# REV4.net
KiCad netlist of a schematic drawn in EAGLE
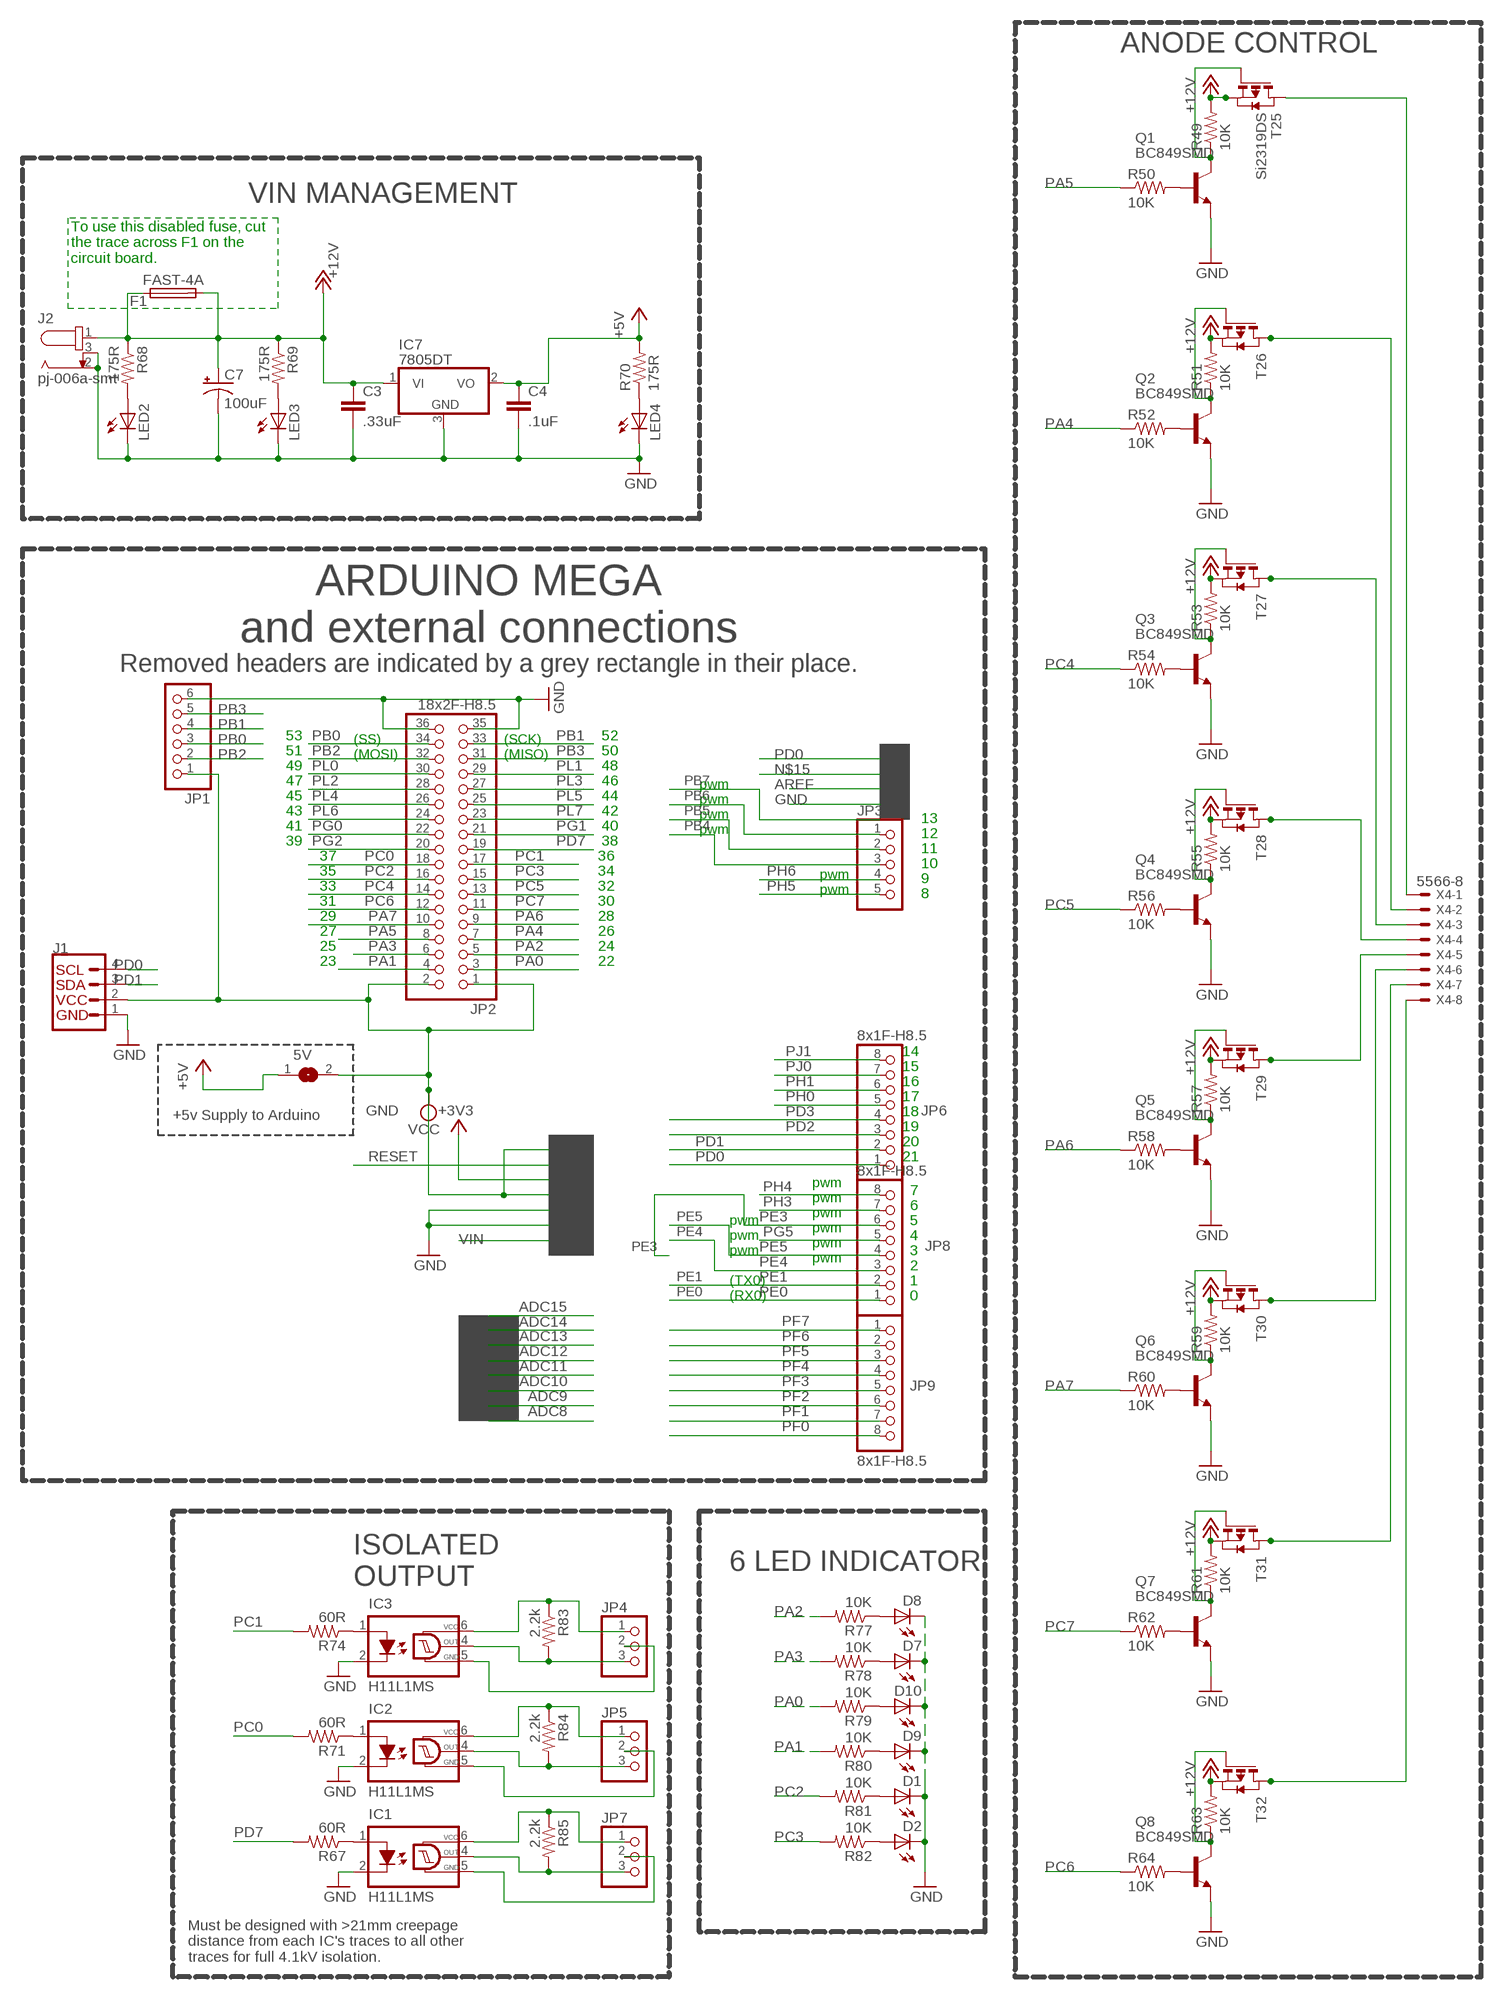
[diagram p0: schematic, sheet 1, part 1 of 2]
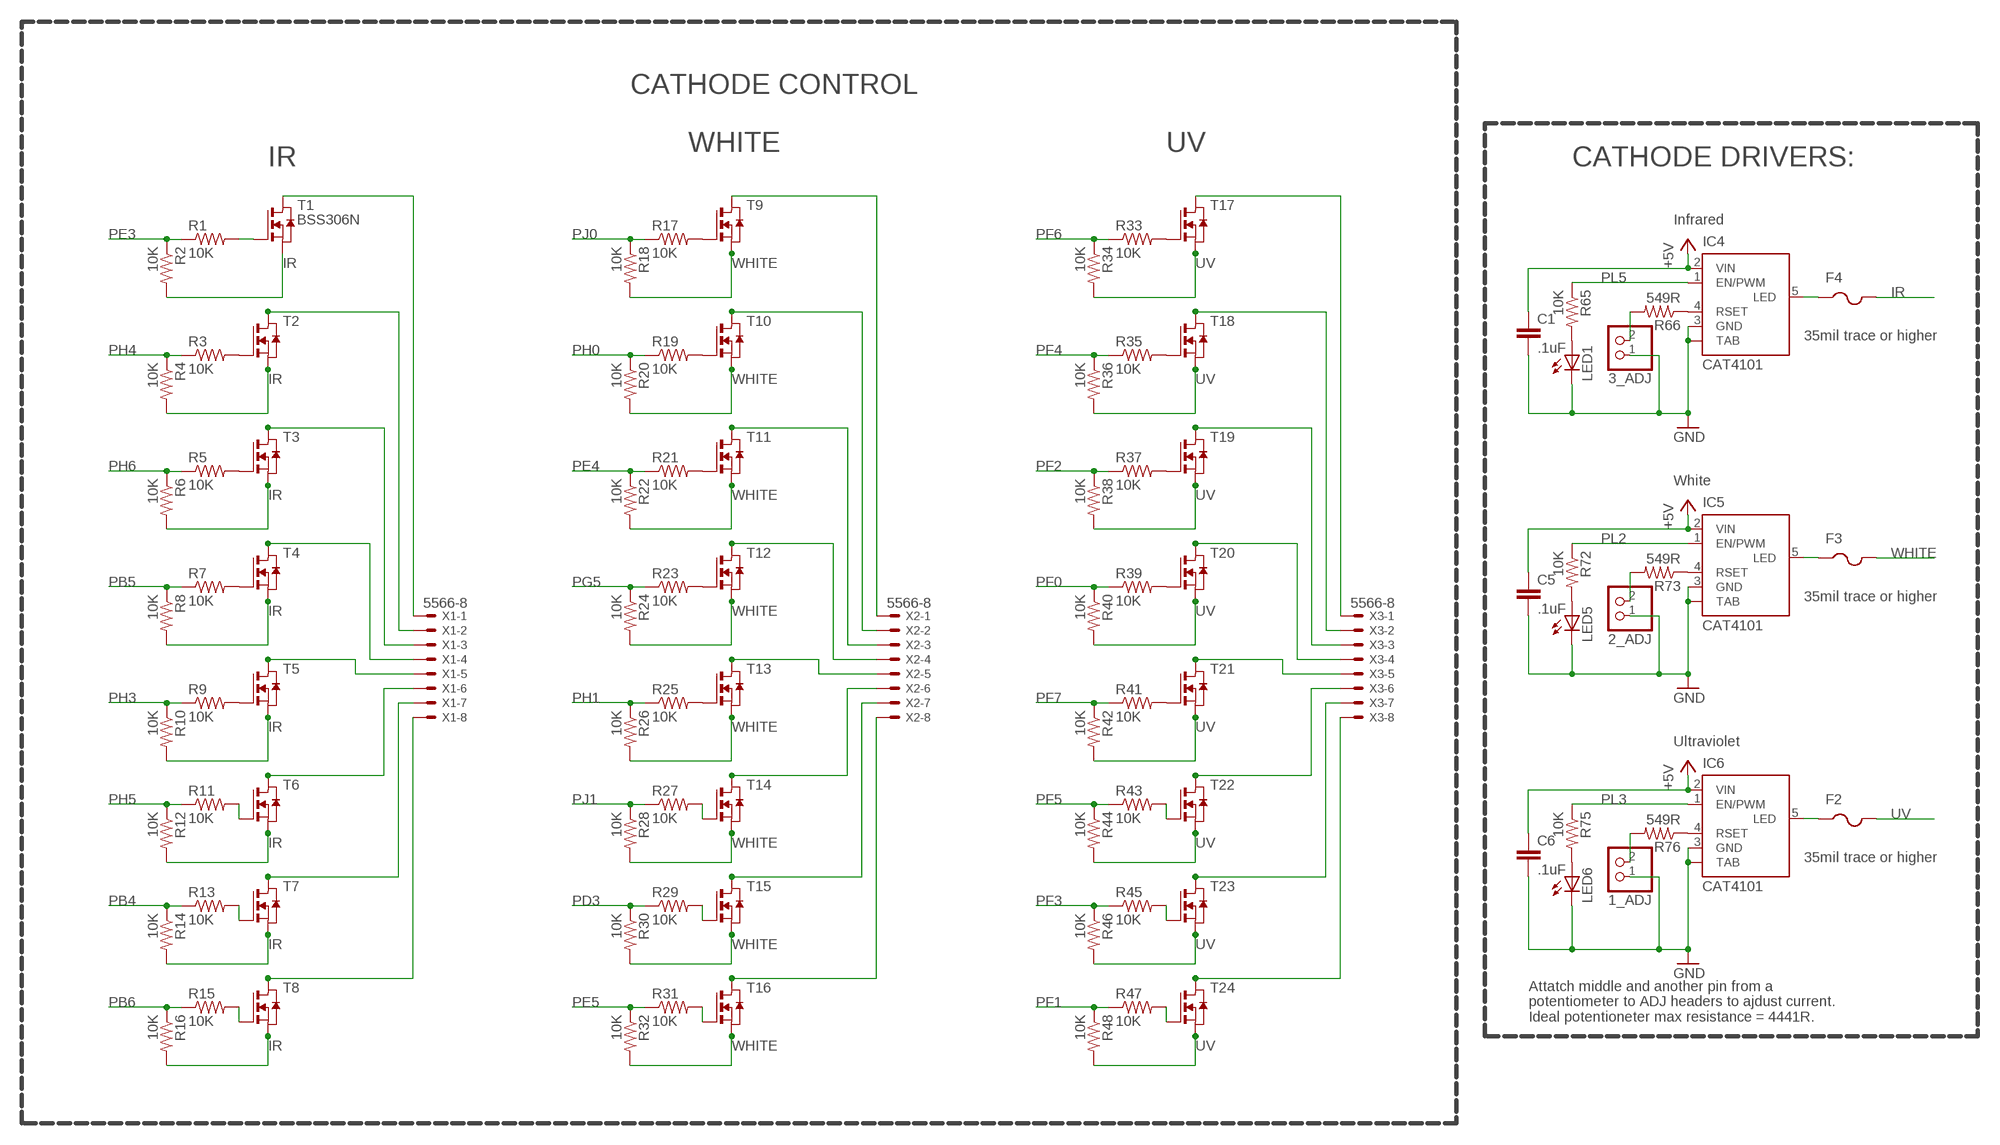
[diagram p1: schematic, sheet 1, part 2 of 2]

(export (version "E")
  (design (tool "Eeschema 10.0.6"))
  (components
    (comp (ref "1_ADJ")
      (value "PINHD-1X2")
      (footprint "eagle-import:1X02")
      (libsource (lib "eagle-import") (part "PINHD-1X2"))
    )
    (comp (ref "2_ADJ")
      (value "PINHD-1X2")
      (footprint "eagle-import:1X02")
      (libsource (lib "eagle-import") (part "PINHD-1X2"))
    )
    (comp (ref "3_ADJ")
      (value "PINHD-1X2")
      (footprint "eagle-import:1X02")
      (libsource (lib "eagle-import") (part "PINHD-1X2"))
    )
    (comp (ref "5V") (value "SJ") (footprint "eagle-import:SJ") (libsource (lib "eagle-import") (part "SJ")))
    (comp (ref "C1")
      (value ".1uF")
      (footprint "eagle-import:C0805")
      (libsource (lib "eagle-import") (part "C"))
    )
    (comp (ref "C3")
      (value ".33uF")
      (footprint "eagle-import:C0805")
      (libsource (lib "eagle-import") (part "C"))
    )
    (comp (ref "C4")
      (value ".1uF")
      (footprint "eagle-import:C0805")
      (libsource (lib "eagle-import") (part "C"))
    )
    (comp (ref "C5")
      (value ".1uF")
      (footprint "eagle-import:C0805")
      (libsource (lib "eagle-import") (part "C"))
    )
    (comp (ref "C6")
      (value ".1uF")
      (footprint "eagle-import:C0805")
      (libsource (lib "eagle-import") (part "C"))
    )
    (comp (ref "C7")
      (value "100uF")
      (footprint "eagle-import:153CLV-0807")
      (libsource (lib "eagle-import") (part "CPOL-US153CLV-0807"))
    )
    (comp (ref "D1")
      (value "LEDSMT1206")
      (footprint "eagle-import:1206")
      (libsource (lib "eagle-import") (part "LEDSMT1206"))
    )
    (comp (ref "D2")
      (value "LEDSMT1206")
      (footprint "eagle-import:1206")
      (libsource (lib "eagle-import") (part "LEDSMT1206"))
    )
    (comp (ref "D7")
      (value "LEDSMT1206")
      (footprint "eagle-import:1206")
      (libsource (lib "eagle-import") (part "LEDSMT1206"))
    )
    (comp (ref "D8")
      (value "LEDSMT1206")
      (footprint "eagle-import:1206")
      (libsource (lib "eagle-import") (part "LEDSMT1206"))
    )
    (comp (ref "D9")
      (value "LEDSMT1206")
      (footprint "eagle-import:1206")
      (libsource (lib "eagle-import") (part "LEDSMT1206"))
    )
    (comp (ref "D10")
      (value "LEDSMT1206")
      (footprint "eagle-import:1206")
      (libsource (lib "eagle-import") (part "LEDSMT1206"))
    )
    (comp (ref "F1")
      (value "FAST-4A")
      (footprint "eagle-import:FUSE_MF-SMDF050")
      (libsource (lib "eagle-import") (part "FUSE_MF-SMDF050"))
    )
    (comp (ref "F2")
      (value "PTCFUSE-1812")
      (footprint "eagle-import:1812")
      (libsource (lib "eagle-import") (part "PTCFUSE-1812"))
    )
    (comp (ref "F3")
      (value "PTCFUSE-1812")
      (footprint "eagle-import:1812")
      (libsource (lib "eagle-import") (part "PTCFUSE-1812"))
    )
    (comp (ref "F4")
      (value "PTCFUSE-1812")
      (footprint "eagle-import:1812")
      (libsource (lib "eagle-import") (part "PTCFUSE-1812"))
    )
    (comp (ref "IC1")
      (value "H11L1MS")
      (footprint "eagle-import:DIL6-SMD")
      (libsource (lib "eagle-import") (part "H11LMS1"))
    )
    (comp (ref "IC2")
      (value "H11L1MS")
      (footprint "eagle-import:DIL6-SMD")
      (libsource (lib "eagle-import") (part "H11LMS1"))
    )
    (comp (ref "IC3")
      (value "H11L1MS")
      (footprint "eagle-import:DIL6-SMD")
      (libsource (lib "eagle-import") (part "H11LMS1"))
    )
    (comp (ref "IC4")
      (value "CAT4101")
      (footprint "eagle-import:TO263_5")
      (fields (field (name "MPN") "CAT4101TV-T75"))
      (libsource (lib "eagle-import") (part "CAT4101"))
    )
    (comp (ref "IC5")
      (value "CAT4101")
      (footprint "eagle-import:TO263_5")
      (fields (field (name "MPN") "CAT4101TV-T75"))
      (libsource (lib "eagle-import") (part "CAT4101"))
    )
    (comp (ref "IC6")
      (value "CAT4101")
      (footprint "eagle-import:TO263_5")
      (fields (field (name "MPN") "CAT4101TV-T75"))
      (libsource (lib "eagle-import") (part "CAT4101"))
    )
    (comp (ref "IC7")
      (value "7805DT")
      (footprint "eagle-import:TO252")
      (libsource (lib "eagle-import") (part "78DT05"))
    )
    (comp (ref "J1")
      (value "I2C_STANDARD")
      (footprint "eagle-import:1X04")
      (libsource (lib "eagle-import") (part "I2C_STANDARD"))
    )
    (comp (ref "J2")
      (value "pj-006a-smt")
      (footprint "eagle-import:69410X210102")
      (libsource (lib "eagle-import") (part "694106210102"))
    )
    (comp (ref "JP1")
      (value "PINHD-1X6")
      (footprint "eagle-import:1X06")
      (libsource (lib "eagle-import") (part "PINHD-1X6"))
    )
    (comp (ref "JP2")
      (value "18x2F-H8.5")
      (footprint "eagle-import:2X18")
      (libsource (lib "eagle-import") (part "PINHD-2X18"))
    )
    (comp (ref "JP3")
      (value "PINHD-1X5")
      (footprint "eagle-import:1X05")
      (libsource (lib "eagle-import") (part "PINHD-1X5"))
    )
    (comp (ref "JP4")
      (value "PINHD-1X3")
      (footprint "eagle-import:1X03")
      (libsource (lib "eagle-import") (part "PINHD-1X3"))
    )
    (comp (ref "JP5")
      (value "PINHD-1X3")
      (footprint "eagle-import:1X03")
      (libsource (lib "eagle-import") (part "PINHD-1X3"))
    )
    (comp (ref "JP6")
      (value "8x1F-H8.5")
      (footprint "eagle-import:1X08")
      (libsource (lib "eagle-import") (part "PINHD-1X8"))
    )
    (comp (ref "JP7")
      (value "PINHD-1X3")
      (footprint "eagle-import:1X03")
      (libsource (lib "eagle-import") (part "PINHD-1X3"))
    )
    (comp (ref "JP8")
      (value "8x1F-H8.5")
      (footprint "eagle-import:1X08")
      (libsource (lib "eagle-import") (part "PINHD-1X8"))
    )
    (comp (ref "JP9")
      (value "8x1F-H8.5")
      (footprint "eagle-import:1X08")
      (libsource (lib "eagle-import") (part "PINHD-1X8"))
    )
    (comp (ref "LED1")
      (value "LEDSMT1206")
      (footprint "eagle-import:1206")
      (libsource (lib "eagle-import") (part "LEDSMT1206"))
    )
    (comp (ref "LED2")
      (value "LEDSMT1206")
      (footprint "eagle-import:1206")
      (libsource (lib "eagle-import") (part "LEDSMT1206"))
    )
    (comp (ref "LED3")
      (value "LEDSMT1206")
      (footprint "eagle-import:1206")
      (libsource (lib "eagle-import") (part "LEDSMT1206"))
    )
    (comp (ref "LED4")
      (value "LEDSMT1206")
      (footprint "eagle-import:1206")
      (libsource (lib "eagle-import") (part "LEDSMT1206"))
    )
    (comp (ref "LED5")
      (value "LEDSMT1206")
      (footprint "eagle-import:1206")
      (libsource (lib "eagle-import") (part "LEDSMT1206"))
    )
    (comp (ref "LED6")
      (value "LEDSMT1206")
      (footprint "eagle-import:1206")
      (libsource (lib "eagle-import") (part "LEDSMT1206"))
    )
    (comp (ref "Q1")
      (value "BC849SMD")
      (footprint "eagle-import:SOT23-BEC")
      (libsource (lib "eagle-import") (part "BC849SMD"))
    )
    (comp (ref "Q2")
      (value "BC849SMD")
      (footprint "eagle-import:SOT23-BEC")
      (libsource (lib "eagle-import") (part "BC849SMD"))
    )
    (comp (ref "Q3")
      (value "BC849SMD")
      (footprint "eagle-import:SOT23-BEC")
      (libsource (lib "eagle-import") (part "BC849SMD"))
    )
    (comp (ref "Q4")
      (value "BC849SMD")
      (footprint "eagle-import:SOT23-BEC")
      (libsource (lib "eagle-import") (part "BC849SMD"))
    )
    (comp (ref "Q5")
      (value "BC849SMD")
      (footprint "eagle-import:SOT23-BEC")
      (libsource (lib "eagle-import") (part "BC849SMD"))
    )
    (comp (ref "Q6")
      (value "BC849SMD")
      (footprint "eagle-import:SOT23-BEC")
      (libsource (lib "eagle-import") (part "BC849SMD"))
    )
    (comp (ref "Q7")
      (value "BC849SMD")
      (footprint "eagle-import:SOT23-BEC")
      (libsource (lib "eagle-import") (part "BC849SMD"))
    )
    (comp (ref "Q8")
      (value "BC849SMD")
      (footprint "eagle-import:SOT23-BEC")
      (libsource (lib "eagle-import") (part "BC849SMD"))
    )
    (comp (ref "R1")
      (value "10K")
      (footprint "eagle-import:R0805")
      (libsource (lib "eagle-import") (part "R-US_R0805"))
    )
    (comp (ref "R2")
      (value "10K")
      (footprint "eagle-import:R0805")
      (libsource (lib "eagle-import") (part "R-US_R0805"))
    )
    (comp (ref "R3")
      (value "10K")
      (footprint "eagle-import:R0805")
      (libsource (lib "eagle-import") (part "R-US_R0805"))
    )
    (comp (ref "R4")
      (value "10K")
      (footprint "eagle-import:R0805")
      (libsource (lib "eagle-import") (part "R-US_R0805"))
    )
    (comp (ref "R5")
      (value "10K")
      (footprint "eagle-import:R0805")
      (libsource (lib "eagle-import") (part "R-US_R0805"))
    )
    (comp (ref "R6")
      (value "10K")
      (footprint "eagle-import:R0805")
      (libsource (lib "eagle-import") (part "R-US_R0805"))
    )
    (comp (ref "R7")
      (value "10K")
      (footprint "eagle-import:R0805")
      (libsource (lib "eagle-import") (part "R-US_R0805"))
    )
    (comp (ref "R8")
      (value "10K")
      (footprint "eagle-import:R0805")
      (libsource (lib "eagle-import") (part "R-US_R0805"))
    )
    (comp (ref "R9")
      (value "10K")
      (footprint "eagle-import:R0805")
      (libsource (lib "eagle-import") (part "R-US_R0805"))
    )
    (comp (ref "R10")
      (value "10K")
      (footprint "eagle-import:R0805")
      (libsource (lib "eagle-import") (part "R-US_R0805"))
    )
    (comp (ref "R11")
      (value "10K")
      (footprint "eagle-import:R0805")
      (libsource (lib "eagle-import") (part "R-US_R0805"))
    )
    (comp (ref "R12")
      (value "10K")
      (footprint "eagle-import:R0805")
      (libsource (lib "eagle-import") (part "R-US_R0805"))
    )
    (comp (ref "R13")
      (value "10K")
      (footprint "eagle-import:R0805")
      (libsource (lib "eagle-import") (part "R-US_R0805"))
    )
    (comp (ref "R14")
      (value "10K")
      (footprint "eagle-import:R0805")
      (libsource (lib "eagle-import") (part "R-US_R0805"))
    )
    (comp (ref "R15")
      (value "10K")
      (footprint "eagle-import:R0805")
      (libsource (lib "eagle-import") (part "R-US_R0805"))
    )
    (comp (ref "R16")
      (value "10K")
      (footprint "eagle-import:R0805")
      (libsource (lib "eagle-import") (part "R-US_R0805"))
    )
    (comp (ref "R17")
      (value "10K")
      (footprint "eagle-import:R0805")
      (libsource (lib "eagle-import") (part "R-US_R0805"))
    )
    (comp (ref "R18")
      (value "10K")
      (footprint "eagle-import:R0805")
      (libsource (lib "eagle-import") (part "R-US_R0805"))
    )
    (comp (ref "R19")
      (value "10K")
      (footprint "eagle-import:R0805")
      (libsource (lib "eagle-import") (part "R-US_R0805"))
    )
    (comp (ref "R20")
      (value "10K")
      (footprint "eagle-import:R0805")
      (libsource (lib "eagle-import") (part "R-US_R0805"))
    )
    (comp (ref "R21")
      (value "10K")
      (footprint "eagle-import:R0805")
      (libsource (lib "eagle-import") (part "R-US_R0805"))
    )
    (comp (ref "R22")
      (value "10K")
      (footprint "eagle-import:R0805")
      (libsource (lib "eagle-import") (part "R-US_R0805"))
    )
    (comp (ref "R23")
      (value "10K")
      (footprint "eagle-import:R0805")
      (libsource (lib "eagle-import") (part "R-US_R0805"))
    )
    (comp (ref "R24")
      (value "10K")
      (footprint "eagle-import:R0805")
      (libsource (lib "eagle-import") (part "R-US_R0805"))
    )
    (comp (ref "R25")
      (value "10K")
      (footprint "eagle-import:R0805")
      (libsource (lib "eagle-import") (part "R-US_R0805"))
    )
    (comp (ref "R26")
      (value "10K")
      (footprint "eagle-import:R0805")
      (libsource (lib "eagle-import") (part "R-US_R0805"))
    )
    (comp (ref "R27")
      (value "10K")
      (footprint "eagle-import:R0805")
      (libsource (lib "eagle-import") (part "R-US_R0805"))
    )
    (comp (ref "R28")
      (value "10K")
      (footprint "eagle-import:R0805")
      (libsource (lib "eagle-import") (part "R-US_R0805"))
    )
    (comp (ref "R29")
      (value "10K")
      (footprint "eagle-import:R0805")
      (libsource (lib "eagle-import") (part "R-US_R0805"))
    )
    (comp (ref "R30")
      (value "10K")
      (footprint "eagle-import:R0805")
      (libsource (lib "eagle-import") (part "R-US_R0805"))
    )
    (comp (ref "R31")
      (value "10K")
      (footprint "eagle-import:R0805")
      (libsource (lib "eagle-import") (part "R-US_R0805"))
    )
    (comp (ref "R32")
      (value "10K")
      (footprint "eagle-import:R0805")
      (libsource (lib "eagle-import") (part "R-US_R0805"))
    )
    (comp (ref "R33")
      (value "10K")
      (footprint "eagle-import:R0805")
      (libsource (lib "eagle-import") (part "R-US_R0805"))
    )
    (comp (ref "R34")
      (value "10K")
      (footprint "eagle-import:R0805")
      (libsource (lib "eagle-import") (part "R-US_R0805"))
    )
    (comp (ref "R35")
      (value "10K")
      (footprint "eagle-import:R0805")
      (libsource (lib "eagle-import") (part "R-US_R0805"))
    )
    (comp (ref "R36")
      (value "10K")
      (footprint "eagle-import:R0805")
      (libsource (lib "eagle-import") (part "R-US_R0805"))
    )
    (comp (ref "R37")
      (value "10K")
      (footprint "eagle-import:R0805")
      (libsource (lib "eagle-import") (part "R-US_R0805"))
    )
    (comp (ref "R38")
      (value "10K")
      (footprint "eagle-import:R0805")
      (libsource (lib "eagle-import") (part "R-US_R0805"))
    )
    (comp (ref "R39")
      (value "10K")
      (footprint "eagle-import:R0805")
      (libsource (lib "eagle-import") (part "R-US_R0805"))
    )
    (comp (ref "R40")
      (value "10K")
      (footprint "eagle-import:R0805")
      (libsource (lib "eagle-import") (part "R-US_R0805"))
    )
    (comp (ref "R41")
      (value "10K")
      (footprint "eagle-import:R0805")
      (libsource (lib "eagle-import") (part "R-US_R0805"))
    )
    (comp (ref "R42")
      (value "10K")
      (footprint "eagle-import:R0805")
      (libsource (lib "eagle-import") (part "R-US_R0805"))
    )
    (comp (ref "R43")
      (value "10K")
      (footprint "eagle-import:R0805")
      (libsource (lib "eagle-import") (part "R-US_R0805"))
    )
    (comp (ref "R44")
      (value "10K")
      (footprint "eagle-import:R0805")
      (libsource (lib "eagle-import") (part "R-US_R0805"))
    )
    (comp (ref "R45")
      (value "10K")
      (footprint "eagle-import:R0805")
      (libsource (lib "eagle-import") (part "R-US_R0805"))
    )
    (comp (ref "R46")
      (value "10K")
      (footprint "eagle-import:R0805")
      (libsource (lib "eagle-import") (part "R-US_R0805"))
    )
    (comp (ref "R47")
      (value "10K")
      (footprint "eagle-import:R0805")
      (libsource (lib "eagle-import") (part "R-US_R0805"))
    )
    (comp (ref "R48")
      (value "10K")
      (footprint "eagle-import:R0805")
      (libsource (lib "eagle-import") (part "R-US_R0805"))
    )
    (comp (ref "R49")
      (value "10K")
      (footprint "eagle-import:R0805")
      (libsource (lib "eagle-import") (part "R-US_R0805"))
    )
    (comp (ref "R50")
      (value "10K")
      (footprint "eagle-import:R0805")
      (libsource (lib "eagle-import") (part "R-US_R0805"))
    )
    (comp (ref "R51")
      (value "10K")
      (footprint "eagle-import:R0805")
      (libsource (lib "eagle-import") (part "R-US_R0805"))
    )
    (comp (ref "R52")
      (value "10K")
      (footprint "eagle-import:R0805")
      (libsource (lib "eagle-import") (part "R-US_R0805"))
    )
    (comp (ref "R53")
      (value "10K")
      (footprint "eagle-import:R0805")
      (libsource (lib "eagle-import") (part "R-US_R0805"))
    )
    (comp (ref "R54")
      (value "10K")
      (footprint "eagle-import:R0805")
      (libsource (lib "eagle-import") (part "R-US_R0805"))
    )
    (comp (ref "R55")
      (value "10K")
      (footprint "eagle-import:R0805")
      (libsource (lib "eagle-import") (part "R-US_R0805"))
    )
    (comp (ref "R56")
      (value "10K")
      (footprint "eagle-import:R0805")
      (libsource (lib "eagle-import") (part "R-US_R0805"))
    )
    (comp (ref "R57")
      (value "10K")
      (footprint "eagle-import:R0805")
      (libsource (lib "eagle-import") (part "R-US_R0805"))
    )
    (comp (ref "R58")
      (value "10K")
      (footprint "eagle-import:R0805")
      (libsource (lib "eagle-import") (part "R-US_R0805"))
    )
    (comp (ref "R59")
      (value "10K")
      (footprint "eagle-import:R0805")
      (libsource (lib "eagle-import") (part "R-US_R0805"))
    )
    (comp (ref "R60")
      (value "10K")
      (footprint "eagle-import:R0805")
      (libsource (lib "eagle-import") (part "R-US_R0805"))
    )
    (comp (ref "R61")
      (value "10K")
      (footprint "eagle-import:R0805")
      (libsource (lib "eagle-import") (part "R-US_R0805"))
    )
    (comp (ref "R62")
      (value "10K")
      (footprint "eagle-import:R0805")
      (libsource (lib "eagle-import") (part "R-US_R0805"))
    )
    (comp (ref "R63")
      (value "10K")
      (footprint "eagle-import:R0805")
      (libsource (lib "eagle-import") (part "R-US_R0805"))
    )
    (comp (ref "R64")
      (value "10K")
      (footprint "eagle-import:R0805")
      (libsource (lib "eagle-import") (part "R-US_R0805"))
    )
    (comp (ref "R65")
      (value "10K")
      (footprint "eagle-import:R0805")
      (libsource (lib "eagle-import") (part "R-US_R0805"))
    )
    (comp (ref "R66")
      (value "549R")
      (footprint "eagle-import:R0805")
      (libsource (lib "eagle-import") (part "R-US_R0805"))
    )
    (comp (ref "R67")
      (value "60R")
      (footprint "eagle-import:R0805")
      (libsource (lib "eagle-import") (part "R-US_R0805"))
    )
    (comp (ref "R68")
      (value "175R")
      (footprint "eagle-import:R0805")
      (libsource (lib "eagle-import") (part "R-US_R0805"))
    )
    (comp (ref "R69")
      (value "175R")
      (footprint "eagle-import:R0805")
      (libsource (lib "eagle-import") (part "R-US_R0805"))
    )
    (comp (ref "R70")
      (value "175R")
      (footprint "eagle-import:R0805")
      (libsource (lib "eagle-import") (part "R-US_R0805"))
    )
    (comp (ref "R71")
      (value "60R")
      (footprint "eagle-import:R0805")
      (libsource (lib "eagle-import") (part "R-US_R0805"))
    )
    (comp (ref "R72")
      (value "10K")
      (footprint "eagle-import:R0805")
      (libsource (lib "eagle-import") (part "R-US_R0805"))
    )
    (comp (ref "R73")
      (value "549R")
      (footprint "eagle-import:R0805")
      (libsource (lib "eagle-import") (part "R-US_R0805"))
    )
    (comp (ref "R74")
      (value "60R")
      (footprint "eagle-import:R0805")
      (libsource (lib "eagle-import") (part "R-US_R0805"))
    )
    (comp (ref "R75")
      (value "10K")
      (footprint "eagle-import:R0805")
      (libsource (lib "eagle-import") (part "R-US_R0805"))
    )
    (comp (ref "R76")
      (value "549R")
      (footprint "eagle-import:R0805")
      (libsource (lib "eagle-import") (part "R-US_R0805"))
    )
    (comp (ref "R77")
      (value "10K")
      (footprint "eagle-import:R0805")
      (libsource (lib "eagle-import") (part "R-US_R0805"))
    )
    (comp (ref "R78")
      (value "10K")
      (footprint "eagle-import:R0805")
      (libsource (lib "eagle-import") (part "R-US_R0805"))
    )
    (comp (ref "R79")
      (value "10K")
      (footprint "eagle-import:R0805")
      (libsource (lib "eagle-import") (part "R-US_R0805"))
    )
    (comp (ref "R80")
      (value "10K")
      (footprint "eagle-import:R0805")
      (libsource (lib "eagle-import") (part "R-US_R0805"))
    )
    (comp (ref "R81")
      (value "10K")
      (footprint "eagle-import:R0805")
      (libsource (lib "eagle-import") (part "R-US_R0805"))
    )
    (comp (ref "R82")
      (value "10K")
      (footprint "eagle-import:R0805")
      (libsource (lib "eagle-import") (part "R-US_R0805"))
    )
    (comp (ref "R83")
      (value "2.2k")
      (footprint "eagle-import:R0805")
      (libsource (lib "eagle-import") (part "R-US_R0805"))
    )
    (comp (ref "R84")
      (value "2.2k")
      (footprint "eagle-import:R0805")
      (libsource (lib "eagle-import") (part "R-US_R0805"))
    )
    (comp (ref "R85")
      (value "2.2k")
      (footprint "eagle-import:R0805")
      (libsource (lib "eagle-import") (part "R-US_R0805"))
    )
    (comp (ref "T1")
      (value "BSS306N")
      (footprint "eagle-import:SOT-23")
      (libsource (lib "eagle-import") (part "NMOSSOT23"))
    )
    (comp (ref "T2")
      (value "NMOSSOT23")
      (footprint "eagle-import:SOT-23")
      (libsource (lib "eagle-import") (part "NMOSSOT23"))
    )
    (comp (ref "T3")
      (value "NMOSSOT23")
      (footprint "eagle-import:SOT-23")
      (libsource (lib "eagle-import") (part "NMOSSOT23"))
    )
    (comp (ref "T4")
      (value "NMOSSOT23")
      (footprint "eagle-import:SOT-23")
      (libsource (lib "eagle-import") (part "NMOSSOT23"))
    )
    (comp (ref "T5")
      (value "NMOSSOT23")
      (footprint "eagle-import:SOT-23")
      (libsource (lib "eagle-import") (part "NMOSSOT23"))
    )
    (comp (ref "T6")
      (value "NMOSSOT23")
      (footprint "eagle-import:SOT-23")
      (libsource (lib "eagle-import") (part "NMOSSOT23"))
    )
    (comp (ref "T7")
      (value "NMOSSOT23")
      (footprint "eagle-import:SOT-23")
      (libsource (lib "eagle-import") (part "NMOSSOT23"))
    )
    (comp (ref "T8")
      (value "NMOSSOT23")
      (footprint "eagle-import:SOT-23")
      (libsource (lib "eagle-import") (part "NMOSSOT23"))
    )
    (comp (ref "T9")
      (value "NMOSSOT23")
      (footprint "eagle-import:SOT-23")
      (libsource (lib "eagle-import") (part "NMOSSOT23"))
    )
    (comp (ref "T10")
      (value "NMOSSOT23")
      (footprint "eagle-import:SOT-23")
      (libsource (lib "eagle-import") (part "NMOSSOT23"))
    )
    (comp (ref "T11")
      (value "NMOSSOT23")
      (footprint "eagle-import:SOT-23")
      (libsource (lib "eagle-import") (part "NMOSSOT23"))
    )
    (comp (ref "T12")
      (value "NMOSSOT23")
      (footprint "eagle-import:SOT-23")
      (libsource (lib "eagle-import") (part "NMOSSOT23"))
    )
    (comp (ref "T13")
      (value "NMOSSOT23")
      (footprint "eagle-import:SOT-23")
      (libsource (lib "eagle-import") (part "NMOSSOT23"))
    )
    (comp (ref "T14")
      (value "NMOSSOT23")
      (footprint "eagle-import:SOT-23")
      (libsource (lib "eagle-import") (part "NMOSSOT23"))
    )
    (comp (ref "T15")
      (value "NMOSSOT23")
      (footprint "eagle-import:SOT-23")
      (libsource (lib "eagle-import") (part "NMOSSOT23"))
    )
    (comp (ref "T16")
      (value "NMOSSOT23")
      (footprint "eagle-import:SOT-23")
      (libsource (lib "eagle-import") (part "NMOSSOT23"))
    )
    (comp (ref "T17")
      (value "NMOSSOT23")
      (footprint "eagle-import:SOT-23")
      (libsource (lib "eagle-import") (part "NMOSSOT23"))
    )
    (comp (ref "T18")
      (value "NMOSSOT23")
      (footprint "eagle-import:SOT-23")
      (libsource (lib "eagle-import") (part "NMOSSOT23"))
    )
    (comp (ref "T19")
      (value "NMOSSOT23")
      (footprint "eagle-import:SOT-23")
      (libsource (lib "eagle-import") (part "NMOSSOT23"))
    )
    (comp (ref "T20")
      (value "NMOSSOT23")
      (footprint "eagle-import:SOT-23")
      (libsource (lib "eagle-import") (part "NMOSSOT23"))
    )
    (comp (ref "T21")
      (value "NMOSSOT23")
      (footprint "eagle-import:SOT-23")
      (libsource (lib "eagle-import") (part "NMOSSOT23"))
    )
    (comp (ref "T22")
      (value "NMOSSOT23")
      (footprint "eagle-import:SOT-23")
      (libsource (lib "eagle-import") (part "NMOSSOT23"))
    )
    (comp (ref "T23")
      (value "NMOSSOT23")
      (footprint "eagle-import:SOT-23")
      (libsource (lib "eagle-import") (part "NMOSSOT23"))
    )
    (comp (ref "T24")
      (value "NMOSSOT23")
      (footprint "eagle-import:SOT-23")
      (libsource (lib "eagle-import") (part "NMOSSOT23"))
    )
    (comp (ref "T25")
      (value "Si2319DS")
      (footprint "eagle-import:SOT-23")
      (libsource (lib "eagle-import") (part "PMOSSOT23"))
    )
    (comp (ref "T26")
      (value "PMOSSOT23")
      (footprint "eagle-import:SOT-23")
      (libsource (lib "eagle-import") (part "PMOSSOT23"))
    )
    (comp (ref "T27")
      (value "PMOSSOT23")
      (footprint "eagle-import:SOT-23")
      (libsource (lib "eagle-import") (part "PMOSSOT23"))
    )
    (comp (ref "T28")
      (value "PMOSSOT23")
      (footprint "eagle-import:SOT-23")
      (libsource (lib "eagle-import") (part "PMOSSOT23"))
    )
    (comp (ref "T29")
      (value "PMOSSOT23")
      (footprint "eagle-import:SOT-23")
      (libsource (lib "eagle-import") (part "PMOSSOT23"))
    )
    (comp (ref "T30")
      (value "PMOSSOT23")
      (footprint "eagle-import:SOT-23")
      (libsource (lib "eagle-import") (part "PMOSSOT23"))
    )
    (comp (ref "T31")
      (value "PMOSSOT23")
      (footprint "eagle-import:SOT-23")
      (libsource (lib "eagle-import") (part "PMOSSOT23"))
    )
    (comp (ref "T32")
      (value "PMOSSOT23")
      (footprint "eagle-import:SOT-23")
      (libsource (lib "eagle-import") (part "PMOSSOT23"))
    )
    (comp (ref "X1")
      (value "5566-8")
      (footprint "eagle-import:5566-8")
      (fields (field (name "MF") "MOLEX"))
      (libsource (lib "eagle-import") (part "5566-8"))
    )
    (comp (ref "X2")
      (value "5566-8")
      (footprint "eagle-import:5566-8")
      (fields (field (name "MF") "MOLEX"))
      (libsource (lib "eagle-import") (part "5566-8"))
    )
    (comp (ref "X3")
      (value "5566-8")
      (footprint "eagle-import:5566-8")
      (fields (field (name "MF") "MOLEX"))
      (libsource (lib "eagle-import") (part "5566-8"))
    )
    (comp (ref "X4")
      (value "5566-8")
      (footprint "eagle-import:5566-8")
      (fields (field (name "MF") "MOLEX"))
      (libsource (lib "eagle-import") (part "5566-8"))
    )
  )
  (nets
    (net (code "2") (name "+5V") (class "Default")
      (node (ref "5V") (pin "1") (pinfunction "1_1") (pintype "passive"))
      (node (ref "C1") (pin "1") (pinfunction "1_1") (pintype "passive"))
      (node (ref "C4") (pin "1") (pinfunction "1_1") (pintype "passive"))
      (node (ref "C5") (pin "1") (pinfunction "1_1") (pintype "passive"))
      (node (ref "C6") (pin "1") (pinfunction "1_1") (pintype "passive"))
      (node (ref "IC4") (pin "2") (pinfunction "VIN_2") (pintype "input"))
      (node (ref "IC5") (pin "2") (pinfunction "VIN_2") (pintype "input"))
      (node (ref "IC6") (pin "2") (pinfunction "VIN_2") (pintype "input"))
      (node (ref "IC7") (pin "2") (pinfunction "VO_2") (pintype "passive"))
      (node (ref "R70") (pin "2") (pinfunction "2_2") (pintype "passive"))
    )
    (net (code "3") (name "+12V") (class "Default")
      (node (ref "C3") (pin "1") (pinfunction "1_1") (pintype "passive"))
      (node (ref "C7") (pin "+") (pinfunction "+_+") (pintype "passive"))
      (node (ref "F1") (pin "1") (pinfunction "1_1") (pintype "passive"))
      (node (ref "F1") (pin "2") (pinfunction "2_2") (pintype "passive"))
      (node (ref "IC7") (pin "1") (pinfunction "VI_1") (pintype "input"))
      (node (ref "J2") (pin "1") (pinfunction "1_1") (pintype "passive"))
      (node (ref "R49") (pin "2") (pinfunction "2_2") (pintype "passive"))
      (node (ref "R51") (pin "2") (pinfunction "2_2") (pintype "passive"))
      (node (ref "R53") (pin "2") (pinfunction "2_2") (pintype "passive"))
      (node (ref "R55") (pin "2") (pinfunction "2_2") (pintype "passive"))
      (node (ref "R57") (pin "2") (pinfunction "2_2") (pintype "passive"))
      (node (ref "R59") (pin "2") (pinfunction "2_2") (pintype "passive"))
      (node (ref "R61") (pin "2") (pinfunction "2_2") (pintype "passive"))
      (node (ref "R63") (pin "2") (pinfunction "2_2") (pintype "passive"))
      (node (ref "R68") (pin "1") (pinfunction "1_1") (pintype "passive"))
      (node (ref "R69") (pin "1") (pinfunction "1_1") (pintype "passive"))
      (node (ref "T25") (pin "2") (pinfunction "S_2") (pintype "passive"))
      (node (ref "T26") (pin "2") (pinfunction "S_2") (pintype "passive"))
      (node (ref "T27") (pin "2") (pinfunction "S_2") (pintype "passive"))
      (node (ref "T28") (pin "2") (pinfunction "S_2") (pintype "passive"))
      (node (ref "T29") (pin "2") (pinfunction "S_2") (pintype "passive"))
      (node (ref "T30") (pin "2") (pinfunction "S_2") (pintype "passive"))
      (node (ref "T31") (pin "2") (pinfunction "S_2") (pintype "passive"))
      (node (ref "T32") (pin "2") (pinfunction "S_2") (pintype "passive"))
    )
    (net (code "13") (name "/IR") (class "Default")
      (node (ref "F4") (pin "2") (pinfunction "2_2") (pintype "passive"))
      (node (ref "R10") (pin "2") (pinfunction "2_2") (pintype "passive"))
      (node (ref "R12") (pin "2") (pinfunction "2_2") (pintype "passive"))
      (node (ref "R14") (pin "2") (pinfunction "2_2") (pintype "passive"))
      (node (ref "R16") (pin "2") (pinfunction "2_2") (pintype "passive"))
      (node (ref "R2") (pin "2") (pinfunction "2_2") (pintype "passive"))
      (node (ref "R4") (pin "2") (pinfunction "2_2") (pintype "passive"))
      (node (ref "R6") (pin "2") (pinfunction "2_2") (pintype "passive"))
      (node (ref "R8") (pin "2") (pinfunction "2_2") (pintype "passive"))
      (node (ref "T1") (pin "2") (pinfunction "S_2") (pintype "passive"))
      (node (ref "T2") (pin "2") (pinfunction "S_2") (pintype "passive"))
      (node (ref "T3") (pin "2") (pinfunction "S_2") (pintype "passive"))
      (node (ref "T4") (pin "2") (pinfunction "S_2") (pintype "passive"))
      (node (ref "T5") (pin "2") (pinfunction "S_2") (pintype "passive"))
      (node (ref "T6") (pin "2") (pinfunction "S_2") (pintype "passive"))
      (node (ref "T7") (pin "2") (pinfunction "S_2") (pintype "passive"))
      (node (ref "T8") (pin "2") (pinfunction "S_2") (pintype "passive"))
    )
    (net (code "15") (name "/PA0") (class "Default")
      (node (ref "JP2") (pin "3") (pinfunction "3_3") (pintype "passive"))
      (node (ref "R79") (pin "2") (pinfunction "2_2") (pintype "passive"))
    )
    (net (code "16") (name "/PA1") (class "Default")
      (node (ref "JP2") (pin "4") (pinfunction "4_4") (pintype "passive"))
      (node (ref "R80") (pin "2") (pinfunction "2_2") (pintype "passive"))
    )
    (net (code "17") (name "/PA2") (class "Default")
      (node (ref "JP2") (pin "5") (pinfunction "5_5") (pintype "passive"))
      (node (ref "R77") (pin "2") (pinfunction "2_2") (pintype "passive"))
    )
    (net (code "18") (name "/PA3") (class "Default")
      (node (ref "JP2") (pin "6") (pinfunction "6_6") (pintype "passive"))
      (node (ref "R78") (pin "2") (pinfunction "2_2") (pintype "passive"))
    )
    (net (code "19") (name "/PA4") (class "Default")
      (node (ref "JP2") (pin "7") (pinfunction "7_7") (pintype "passive"))
      (node (ref "R52") (pin "1") (pinfunction "1_1") (pintype "passive"))
    )
    (net (code "20") (name "/PA5") (class "Default")
      (node (ref "JP2") (pin "8") (pinfunction "8_8") (pintype "passive"))
      (node (ref "R50") (pin "1") (pinfunction "1_1") (pintype "passive"))
    )
    (net (code "21") (name "/PA6") (class "Default")
      (node (ref "JP2") (pin "9") (pinfunction "9_9") (pintype "passive"))
      (node (ref "R58") (pin "1") (pinfunction "1_1") (pintype "passive"))
    )
    (net (code "22") (name "/PA7") (class "Default")
      (node (ref "JP2") (pin "10") (pinfunction "10_10") (pintype "passive"))
      (node (ref "R60") (pin "1") (pinfunction "1_1") (pintype "passive"))
    )
    (net (code "23") (name "/PB0") (class "Default")
      (node (ref "JP1") (pin "3") (pinfunction "3_3") (pintype "passive"))
      (node (ref "JP2") (pin "34") (pinfunction "34_34") (pintype "passive"))
    )
    (net (code "24") (name "/PB1") (class "Default")
      (node (ref "JP1") (pin "4") (pinfunction "4_4") (pintype "passive"))
      (node (ref "JP2") (pin "33") (pinfunction "33_33") (pintype "passive"))
    )
    (net (code "25") (name "/PB2") (class "Default")
      (node (ref "JP1") (pin "2") (pinfunction "2_2") (pintype "passive"))
      (node (ref "JP2") (pin "32") (pinfunction "32_32") (pintype "passive"))
    )
    (net (code "26") (name "/PB3") (class "Default")
      (node (ref "JP1") (pin "5") (pinfunction "5_5") (pintype "passive"))
      (node (ref "JP2") (pin "31") (pinfunction "31_31") (pintype "passive"))
    )
    (net (code "27") (name "/PB4") (class "Default")
      (node (ref "JP3") (pin "3") (pinfunction "3_3") (pintype "passive"))
      (node (ref "R13") (pin "1") (pinfunction "1_1") (pintype "passive"))
      (node (ref "R14") (pin "1") (pinfunction "1_1") (pintype "passive"))
    )
    (net (code "28") (name "/PB5") (class "Default")
      (node (ref "JP3") (pin "2") (pinfunction "2_2") (pintype "passive"))
      (node (ref "R7") (pin "1") (pinfunction "1_1") (pintype "passive"))
      (node (ref "R8") (pin "1") (pinfunction "1_1") (pintype "passive"))
    )
    (net (code "29") (name "/PB6") (class "Default")
      (node (ref "JP3") (pin "1") (pinfunction "1_1") (pintype "passive"))
      (node (ref "R15") (pin "1") (pinfunction "1_1") (pintype "passive"))
      (node (ref "R16") (pin "1") (pinfunction "1_1") (pintype "passive"))
    )
    (net (code "31") (name "/PC0") (class "Default")
      (node (ref "JP2") (pin "18") (pinfunction "18_18") (pintype "passive"))
      (node (ref "R71") (pin "2") (pinfunction "2_2") (pintype "passive"))
    )
    (net (code "32") (name "/PC1") (class "Default")
      (node (ref "JP2") (pin "17") (pinfunction "17_17") (pintype "passive"))
      (node (ref "R74") (pin "2") (pinfunction "2_2") (pintype "passive"))
    )
    (net (code "33") (name "/PC2") (class "Default")
      (node (ref "JP2") (pin "16") (pinfunction "16_16") (pintype "passive"))
      (node (ref "R81") (pin "2") (pinfunction "2_2") (pintype "passive"))
    )
    (net (code "34") (name "/PC3") (class "Default")
      (node (ref "JP2") (pin "15") (pinfunction "15_15") (pintype "passive"))
      (node (ref "R82") (pin "2") (pinfunction "2_2") (pintype "passive"))
    )
    (net (code "35") (name "/PC4") (class "Default")
      (node (ref "JP2") (pin "14") (pinfunction "14_14") (pintype "passive"))
      (node (ref "R54") (pin "1") (pinfunction "1_1") (pintype "passive"))
    )
    (net (code "36") (name "/PC5") (class "Default")
      (node (ref "JP2") (pin "13") (pinfunction "13_13") (pintype "passive"))
      (node (ref "R56") (pin "1") (pinfunction "1_1") (pintype "passive"))
    )
    (net (code "37") (name "/PC6") (class "Default")
      (node (ref "JP2") (pin "12") (pinfunction "12_12") (pintype "passive"))
      (node (ref "R64") (pin "1") (pinfunction "1_1") (pintype "passive"))
    )
    (net (code "38") (name "/PC7") (class "Default")
      (node (ref "JP2") (pin "11") (pinfunction "11_11") (pintype "passive"))
      (node (ref "R62") (pin "1") (pinfunction "1_1") (pintype "passive"))
    )
    (net (code "39") (name "/PD0") (class "Default")
      (node (ref "J1") (pin "4") (pinfunction "4_4") (pintype "passive"))
      (node (ref "JP6") (pin "1") (pinfunction "1_1") (pintype "passive"))
    )
    (net (code "40") (name "/PD1") (class "Default")
      (node (ref "J1") (pin "3") (pinfunction "3_3") (pintype "passive"))
      (node (ref "JP6") (pin "2") (pinfunction "2_2") (pintype "passive"))
    )
    (net (code "41") (name "/PD2") (class "Default")
      (node (ref "JP6") (pin "3") (pinfunction "3_3") (pintype "passive"))
    )
    (net (code "42") (name "/PD3") (class "Default")
      (node (ref "JP6") (pin "4") (pinfunction "4_4") (pintype "passive"))
      (node (ref "R29") (pin "1") (pinfunction "1_1") (pintype "passive"))
      (node (ref "R30") (pin "1") (pinfunction "1_1") (pintype "passive"))
    )
    (net (code "43") (name "/PD7") (class "Default")
      (node (ref "JP2") (pin "19") (pinfunction "19_19") (pintype "passive"))
      (node (ref "R67") (pin "2") (pinfunction "2_2") (pintype "passive"))
    )
    (net (code "44") (name "/PE0") (class "Default")
      (node (ref "JP8") (pin "1") (pinfunction "1_1") (pintype "passive"))
    )
    (net (code "45") (name "/PE1") (class "Default")
      (node (ref "JP8") (pin "2") (pinfunction "2_2") (pintype "passive"))
    )
    (net (code "46") (name "/PE3") (class "Default")
      (node (ref "JP8") (pin "6") (pinfunction "6_6") (pintype "passive"))
      (node (ref "R1") (pin "1") (pinfunction "1_1") (pintype "passive"))
      (node (ref "R2") (pin "1") (pinfunction "1_1") (pintype "passive"))
    )
    (net (code "47") (name "/PE4") (class "Default")
      (node (ref "JP8") (pin "3") (pinfunction "3_3") (pintype "passive"))
      (node (ref "R21") (pin "1") (pinfunction "1_1") (pintype "passive"))
      (node (ref "R22") (pin "1") (pinfunction "1_1") (pintype "passive"))
    )
    (net (code "48") (name "/PE5") (class "Default")
      (node (ref "JP8") (pin "4") (pinfunction "4_4") (pintype "passive"))
      (node (ref "R31") (pin "1") (pinfunction "1_1") (pintype "passive"))
      (node (ref "R32") (pin "1") (pinfunction "1_1") (pintype "passive"))
    )
    (net (code "49") (name "/PF0") (class "Default")
      (node (ref "JP9") (pin "8") (pinfunction "8_8") (pintype "passive"))
      (node (ref "R39") (pin "1") (pinfunction "1_1") (pintype "passive"))
      (node (ref "R40") (pin "1") (pinfunction "1_1") (pintype "passive"))
    )
    (net (code "50") (name "/PF1") (class "Default")
      (node (ref "JP9") (pin "7") (pinfunction "7_7") (pintype "passive"))
      (node (ref "R47") (pin "1") (pinfunction "1_1") (pintype "passive"))
      (node (ref "R48") (pin "1") (pinfunction "1_1") (pintype "passive"))
    )
    (net (code "51") (name "/PF2") (class "Default")
      (node (ref "JP9") (pin "6") (pinfunction "6_6") (pintype "passive"))
      (node (ref "R37") (pin "1") (pinfunction "1_1") (pintype "passive"))
      (node (ref "R38") (pin "1") (pinfunction "1_1") (pintype "passive"))
    )
    (net (code "52") (name "/PF3") (class "Default")
      (node (ref "JP9") (pin "5") (pinfunction "5_5") (pintype "passive"))
      (node (ref "R45") (pin "1") (pinfunction "1_1") (pintype "passive"))
      (node (ref "R46") (pin "1") (pinfunction "1_1") (pintype "passive"))
    )
    (net (code "53") (name "/PF4") (class "Default")
      (node (ref "JP9") (pin "4") (pinfunction "4_4") (pintype "passive"))
      (node (ref "R35") (pin "1") (pinfunction "1_1") (pintype "passive"))
      (node (ref "R36") (pin "1") (pinfunction "1_1") (pintype "passive"))
    )
    (net (code "54") (name "/PF5") (class "Default")
      (node (ref "JP9") (pin "3") (pinfunction "3_3") (pintype "passive"))
      (node (ref "R43") (pin "1") (pinfunction "1_1") (pintype "passive"))
      (node (ref "R44") (pin "1") (pinfunction "1_1") (pintype "passive"))
    )
    (net (code "55") (name "/PF6") (class "Default")
      (node (ref "JP9") (pin "2") (pinfunction "2_2") (pintype "passive"))
      (node (ref "R33") (pin "1") (pinfunction "1_1") (pintype "passive"))
      (node (ref "R34") (pin "1") (pinfunction "1_1") (pintype "passive"))
    )
    (net (code "56") (name "/PF7") (class "Default")
      (node (ref "JP9") (pin "1") (pinfunction "1_1") (pintype "passive"))
      (node (ref "R41") (pin "1") (pinfunction "1_1") (pintype "passive"))
      (node (ref "R42") (pin "1") (pinfunction "1_1") (pintype "passive"))
    )
    (net (code "57") (name "/PG0") (class "Default")
      (node (ref "JP2") (pin "22") (pinfunction "22_22") (pintype "passive"))
    )
    (net (code "58") (name "/PG1") (class "Default")
      (node (ref "JP2") (pin "21") (pinfunction "21_21") (pintype "passive"))
    )
    (net (code "59") (name "/PG2") (class "Default")
      (node (ref "JP2") (pin "20") (pinfunction "20_20") (pintype "passive"))
    )
    (net (code "60") (name "/PG5") (class "Default")
      (node (ref "JP8") (pin "5") (pinfunction "5_5") (pintype "passive"))
      (node (ref "R23") (pin "1") (pinfunction "1_1") (pintype "passive"))
      (node (ref "R24") (pin "1") (pinfunction "1_1") (pintype "passive"))
    )
    (net (code "61") (name "/PH0") (class "Default")
      (node (ref "JP6") (pin "5") (pinfunction "5_5") (pintype "passive"))
      (node (ref "R19") (pin "1") (pinfunction "1_1") (pintype "passive"))
      (node (ref "R20") (pin "1") (pinfunction "1_1") (pintype "passive"))
    )
    (net (code "62") (name "/PH1") (class "Default")
      (node (ref "JP6") (pin "6") (pinfunction "6_6") (pintype "passive"))
      (node (ref "R25") (pin "1") (pinfunction "1_1") (pintype "passive"))
      (node (ref "R26") (pin "1") (pinfunction "1_1") (pintype "passive"))
    )
    (net (code "63") (name "/PH3") (class "Default")
      (node (ref "JP8") (pin "7") (pinfunction "7_7") (pintype "passive"))
      (node (ref "R10") (pin "1") (pinfunction "1_1") (pintype "passive"))
      (node (ref "R9") (pin "1") (pinfunction "1_1") (pintype "passive"))
    )
    (net (code "64") (name "/PH4") (class "Default")
      (node (ref "JP8") (pin "8") (pinfunction "8_8") (pintype "passive"))
      (node (ref "R3") (pin "1") (pinfunction "1_1") (pintype "passive"))
      (node (ref "R4") (pin "1") (pinfunction "1_1") (pintype "passive"))
    )
    (net (code "65") (name "/PH5") (class "Default")
      (node (ref "JP3") (pin "5") (pinfunction "5_5") (pintype "passive"))
      (node (ref "R11") (pin "1") (pinfunction "1_1") (pintype "passive"))
      (node (ref "R12") (pin "1") (pinfunction "1_1") (pintype "passive"))
    )
    (net (code "66") (name "/PH6") (class "Default")
      (node (ref "JP3") (pin "4") (pinfunction "4_4") (pintype "passive"))
      (node (ref "R5") (pin "1") (pinfunction "1_1") (pintype "passive"))
      (node (ref "R6") (pin "1") (pinfunction "1_1") (pintype "passive"))
    )
    (net (code "67") (name "/PJ0") (class "Default")
      (node (ref "JP6") (pin "7") (pinfunction "7_7") (pintype "passive"))
      (node (ref "R17") (pin "1") (pinfunction "1_1") (pintype "passive"))
      (node (ref "R18") (pin "1") (pinfunction "1_1") (pintype "passive"))
    )
    (net (code "68") (name "/PJ1") (class "Default")
      (node (ref "JP6") (pin "8") (pinfunction "8_8") (pintype "passive"))
      (node (ref "R27") (pin "1") (pinfunction "1_1") (pintype "passive"))
      (node (ref "R28") (pin "1") (pinfunction "1_1") (pintype "passive"))
    )
    (net (code "69") (name "/PL0") (class "Default")
      (node (ref "JP2") (pin "30") (pinfunction "30_30") (pintype "passive"))
    )
    (net (code "70") (name "/PL1") (class "Default")
      (node (ref "JP2") (pin "29") (pinfunction "29_29") (pintype "passive"))
    )
    (net (code "71") (name "/PL2") (class "Default")
      (node (ref "IC5") (pin "1") (pinfunction "EN/PWM_1") (pintype "input"))
      (node (ref "JP2") (pin "28") (pinfunction "28_28") (pintype "passive"))
      (node (ref "R72") (pin "1") (pinfunction "1_1") (pintype "passive"))
    )
    (net (code "72") (name "/PL3") (class "Default")
      (node (ref "IC6") (pin "1") (pinfunction "EN/PWM_1") (pintype "input"))
      (node (ref "JP2") (pin "27") (pinfunction "27_27") (pintype "passive"))
      (node (ref "R75") (pin "1") (pinfunction "1_1") (pintype "passive"))
    )
    (net (code "73") (name "/PL4") (class "Default")
      (node (ref "JP2") (pin "26") (pinfunction "26_26") (pintype "passive"))
    )
    (net (code "74") (name "/PL5") (class "Default")
      (node (ref "IC4") (pin "1") (pinfunction "EN/PWM_1") (pintype "input"))
      (node (ref "JP2") (pin "25") (pinfunction "25_25") (pintype "passive"))
      (node (ref "R65") (pin "1") (pinfunction "1_1") (pintype "passive"))
    )
    (net (code "75") (name "/PL6") (class "Default")
      (node (ref "JP2") (pin "24") (pinfunction "24_24") (pintype "passive"))
    )
    (net (code "76") (name "/PL7") (class "Default")
      (node (ref "JP2") (pin "23") (pinfunction "23_23") (pintype "passive"))
    )
    (net (code "78") (name "/UV") (class "Default")
      (node (ref "F2") (pin "2") (pinfunction "2_2") (pintype "passive"))
      (node (ref "R34") (pin "2") (pinfunction "2_2") (pintype "passive"))
      (node (ref "R36") (pin "2") (pinfunction "2_2") (pintype "passive"))
      (node (ref "R38") (pin "2") (pinfunction "2_2") (pintype "passive"))
      (node (ref "R40") (pin "2") (pinfunction "2_2") (pintype "passive"))
      (node (ref "R42") (pin "2") (pinfunction "2_2") (pintype "passive"))
      (node (ref "R44") (pin "2") (pinfunction "2_2") (pintype "passive"))
      (node (ref "R46") (pin "2") (pinfunction "2_2") (pintype "passive"))
      (node (ref "R48") (pin "2") (pinfunction "2_2") (pintype "passive"))
      (node (ref "T17") (pin "2") (pinfunction "S_2") (pintype "passive"))
      (node (ref "T18") (pin "2") (pinfunction "S_2") (pintype "passive"))
      (node (ref "T19") (pin "2") (pinfunction "S_2") (pintype "passive"))
      (node (ref "T20") (pin "2") (pinfunction "S_2") (pintype "passive"))
      (node (ref "T21") (pin "2") (pinfunction "S_2") (pintype "passive"))
      (node (ref "T22") (pin "2") (pinfunction "S_2") (pintype "passive"))
      (node (ref "T23") (pin "2") (pinfunction "S_2") (pintype "passive"))
      (node (ref "T24") (pin "2") (pinfunction "S_2") (pintype "passive"))
    )
    (net (code "80") (name "/WHITE") (class "Default")
      (node (ref "F3") (pin "2") (pinfunction "2_2") (pintype "passive"))
      (node (ref "R18") (pin "2") (pinfunction "2_2") (pintype "passive"))
      (node (ref "R20") (pin "2") (pinfunction "2_2") (pintype "passive"))
      (node (ref "R22") (pin "2") (pinfunction "2_2") (pintype "passive"))
      (node (ref "R24") (pin "2") (pinfunction "2_2") (pintype "passive"))
      (node (ref "R26") (pin "2") (pinfunction "2_2") (pintype "passive"))
      (node (ref "R28") (pin "2") (pinfunction "2_2") (pintype "passive"))
      (node (ref "R30") (pin "2") (pinfunction "2_2") (pintype "passive"))
      (node (ref "R32") (pin "2") (pinfunction "2_2") (pintype "passive"))
      (node (ref "T10") (pin "2") (pinfunction "S_2") (pintype "passive"))
      (node (ref "T11") (pin "2") (pinfunction "S_2") (pintype "passive"))
      (node (ref "T12") (pin "2") (pinfunction "S_2") (pintype "passive"))
      (node (ref "T13") (pin "2") (pinfunction "S_2") (pintype "passive"))
      (node (ref "T14") (pin "2") (pinfunction "S_2") (pintype "passive"))
      (node (ref "T15") (pin "2") (pinfunction "S_2") (pintype "passive"))
      (node (ref "T16") (pin "2") (pinfunction "S_2") (pintype "passive"))
      (node (ref "T9") (pin "2") (pinfunction "S_2") (pintype "passive"))
    )
    (net (code "81") (name "GND") (class "Default")
      (node (ref "1_ADJ") (pin "1") (pinfunction "1_1") (pintype "passive"))
      (node (ref "2_ADJ") (pin "1") (pinfunction "1_1") (pintype "passive"))
      (node (ref "3_ADJ") (pin "1") (pinfunction "1_1") (pintype "passive"))
      (node (ref "C1") (pin "2") (pinfunction "2_2") (pintype "passive"))
      (node (ref "C3") (pin "2") (pinfunction "2_2") (pintype "passive"))
      (node (ref "C4") (pin "2") (pinfunction "2_2") (pintype "passive"))
      (node (ref "C5") (pin "2") (pinfunction "2_2") (pintype "passive"))
      (node (ref "C6") (pin "2") (pinfunction "2_2") (pintype "passive"))
      (node (ref "C7") (pin "-") (pinfunction "-_-") (pintype "passive"))
      (node (ref "D1") (pin "C") (pinfunction "C_C") (pintype "passive"))
      (node (ref "D10") (pin "C") (pinfunction "C_C") (pintype "passive"))
      (node (ref "D2") (pin "C") (pinfunction "C_C") (pintype "passive"))
      (node (ref "D7") (pin "C") (pinfunction "C_C") (pintype "passive"))
      (node (ref "D8") (pin "C") (pinfunction "C_C") (pintype "passive"))
      (node (ref "D9") (pin "C") (pinfunction "C_C") (pintype "passive"))
      (node (ref "IC1") (pin "2") (pinfunction "C_2") (pintype "passive"))
      (node (ref "IC2") (pin "2") (pinfunction "C_2") (pintype "passive"))
      (node (ref "IC3") (pin "2") (pinfunction "C_2") (pintype "passive"))
      (node (ref "IC4") (pin "3") (pinfunction "GND_3") (pintype "power_in"))
      (node (ref "IC4") (pin "TAB") (pinfunction "TAB_TAB") (pintype "passive"))
      (node (ref "IC5") (pin "3") (pinfunction "GND_3") (pintype "power_in"))
      (node (ref "IC5") (pin "TAB") (pinfunction "TAB_TAB") (pintype "passive"))
      (node (ref "IC6") (pin "3") (pinfunction "GND_3") (pintype "power_in"))
      (node (ref "IC6") (pin "TAB") (pinfunction "TAB_TAB") (pintype "passive"))
      (node (ref "IC7") (pin "3") (pinfunction "GND_3") (pintype "passive"))
      (node (ref "J1") (pin "1") (pinfunction "1_1") (pintype "power_in"))
      (node (ref "J2") (pin "2") (pinfunction "2_2") (pintype "passive"))
      (node (ref "J2") (pin "3") (pinfunction "3_3") (pintype "passive"))
      (node (ref "JP1") (pin "6") (pinfunction "6_6") (pintype "passive"))
      (node (ref "JP2") (pin "35") (pinfunction "35_35") (pintype "passive"))
      (node (ref "JP2") (pin "36") (pinfunction "36_36") (pintype "passive"))
      (node (ref "LED1") (pin "C") (pinfunction "C_C") (pintype "passive"))
      (node (ref "LED2") (pin "C") (pinfunction "C_C") (pintype "passive"))
      (node (ref "LED3") (pin "C") (pinfunction "C_C") (pintype "passive"))
      (node (ref "LED4") (pin "C") (pinfunction "C_C") (pintype "passive"))
      (node (ref "LED5") (pin "C") (pinfunction "C_C") (pintype "passive"))
      (node (ref "LED6") (pin "C") (pinfunction "C_C") (pintype "passive"))
      (node (ref "Q1") (pin "E") (pinfunction "E_E") (pintype "passive"))
      (node (ref "Q2") (pin "E") (pinfunction "E_E") (pintype "passive"))
      (node (ref "Q3") (pin "E") (pinfunction "E_E") (pintype "passive"))
      (node (ref "Q4") (pin "E") (pinfunction "E_E") (pintype "passive"))
      (node (ref "Q5") (pin "E") (pinfunction "E_E") (pintype "passive"))
      (node (ref "Q6") (pin "E") (pinfunction "E_E") (pintype "passive"))
      (node (ref "Q7") (pin "E") (pinfunction "E_E") (pintype "passive"))
      (node (ref "Q8") (pin "E") (pinfunction "E_E") (pintype "passive"))
    )
    (net (code "82") (name "Net-(1_ADJ-Pad2)") (class "Default")
      (node (ref "1_ADJ") (pin "2") (pinfunction "2_2") (pintype "passive"))
      (node (ref "R76") (pin "2") (pinfunction "2_2") (pintype "passive"))
    )
    (net (code "83") (name "Net-(2_ADJ-Pad2)") (class "Default")
      (node (ref "2_ADJ") (pin "2") (pinfunction "2_2") (pintype "passive"))
      (node (ref "R73") (pin "2") (pinfunction "2_2") (pintype "passive"))
    )
    (net (code "84") (name "Net-(3_ADJ-Pad2)") (class "Default")
      (node (ref "3_ADJ") (pin "2") (pinfunction "2_2") (pintype "passive"))
      (node (ref "R66") (pin "2") (pinfunction "2_2") (pintype "passive"))
    )
    (net (code "85") (name "Net-(D1-PadA)") (class "Default")
      (node (ref "D1") (pin "A") (pinfunction "A_A") (pintype "passive"))
      (node (ref "R81") (pin "1") (pinfunction "1_1") (pintype "passive"))
    )
    (net (code "86") (name "Net-(D2-PadA)") (class "Default")
      (node (ref "D2") (pin "A") (pinfunction "A_A") (pintype "passive"))
      (node (ref "R82") (pin "1") (pinfunction "1_1") (pintype "passive"))
    )
    (net (code "87") (name "Net-(D7-PadA)") (class "Default")
      (node (ref "D7") (pin "A") (pinfunction "A_A") (pintype "passive"))
      (node (ref "R78") (pin "1") (pinfunction "1_1") (pintype "passive"))
    )
    (net (code "88") (name "Net-(D8-PadA)") (class "Default")
      (node (ref "D8") (pin "A") (pinfunction "A_A") (pintype "passive"))
      (node (ref "R77") (pin "1") (pinfunction "1_1") (pintype "passive"))
    )
    (net (code "89") (name "Net-(D9-PadA)") (class "Default")
      (node (ref "D9") (pin "A") (pinfunction "A_A") (pintype "passive"))
      (node (ref "R80") (pin "1") (pinfunction "1_1") (pintype "passive"))
    )
    (net (code "90") (name "Net-(D10-PadA)") (class "Default")
      (node (ref "D10") (pin "A") (pinfunction "A_A") (pintype "passive"))
      (node (ref "R79") (pin "1") (pinfunction "1_1") (pintype "passive"))
    )
    (net (code "91") (name "Net-(IC1-A)") (class "Default")
      (node (ref "IC1") (pin "1") (pinfunction "A_1") (pintype "passive"))
      (node (ref "R67") (pin "1") (pinfunction "1_1") (pintype "passive"))
    )
    (net (code "92") (name "Net-(IC1-GND)") (class "Default")
      (node (ref "IC1") (pin "5") (pinfunction "GND_5") (pintype "power_in"))
      (node (ref "JP7") (pin "2") (pinfunction "2_2") (pintype "passive"))
    )
    (net (code "93") (name "Net-(IC1-OUT)") (class "Default")
      (node (ref "IC1") (pin "4") (pinfunction "OUT_4") (pintype "output"))
      (node (ref "JP7") (pin "3") (pinfunction "3_3") (pintype "passive"))
      (node (ref "R85") (pin "2") (pinfunction "2_2") (pintype "passive"))
    )
    (net (code "94") (name "Net-(IC1-VCC)") (class "Default")
      (node (ref "IC1") (pin "6") (pinfunction "VCC_6") (pintype "power_in"))
      (node (ref "JP7") (pin "1") (pinfunction "1_1") (pintype "passive"))
      (node (ref "R85") (pin "1") (pinfunction "1_1") (pintype "passive"))
    )
    (net (code "95") (name "Net-(IC2-A)") (class "Default")
      (node (ref "IC2") (pin "1") (pinfunction "A_1") (pintype "passive"))
      (node (ref "R71") (pin "1") (pinfunction "1_1") (pintype "passive"))
    )
    (net (code "96") (name "Net-(IC2-GND)") (class "Default")
      (node (ref "IC2") (pin "5") (pinfunction "GND_5") (pintype "power_in"))
      (node (ref "JP5") (pin "2") (pinfunction "2_2") (pintype "passive"))
    )
    (net (code "97") (name "Net-(IC2-OUT)") (class "Default")
      (node (ref "IC2") (pin "4") (pinfunction "OUT_4") (pintype "output"))
      (node (ref "JP5") (pin "3") (pinfunction "3_3") (pintype "passive"))
      (node (ref "R84") (pin "2") (pinfunction "2_2") (pintype "passive"))
    )
    (net (code "98") (name "Net-(IC2-VCC)") (class "Default")
      (node (ref "IC2") (pin "6") (pinfunction "VCC_6") (pintype "power_in"))
      (node (ref "JP5") (pin "1") (pinfunction "1_1") (pintype "passive"))
      (node (ref "R84") (pin "1") (pinfunction "1_1") (pintype "passive"))
    )
    (net (code "99") (name "Net-(IC3-A)") (class "Default")
      (node (ref "IC3") (pin "1") (pinfunction "A_1") (pintype "passive"))
      (node (ref "R74") (pin "1") (pinfunction "1_1") (pintype "passive"))
    )
    (net (code "100") (name "Net-(IC3-GND)") (class "Default")
      (node (ref "IC3") (pin "5") (pinfunction "GND_5") (pintype "power_in"))
      (node (ref "JP4") (pin "2") (pinfunction "2_2") (pintype "passive"))
    )
    (net (code "101") (name "Net-(IC3-OUT)") (class "Default")
      (node (ref "IC3") (pin "4") (pinfunction "OUT_4") (pintype "output"))
      (node (ref "JP4") (pin "3") (pinfunction "3_3") (pintype "passive"))
      (node (ref "R83") (pin "2") (pinfunction "2_2") (pintype "passive"))
    )
    (net (code "102") (name "Net-(IC3-VCC)") (class "Default")
      (node (ref "IC3") (pin "6") (pinfunction "VCC_6") (pintype "power_in"))
      (node (ref "JP4") (pin "1") (pinfunction "1_1") (pintype "passive"))
      (node (ref "R83") (pin "1") (pinfunction "1_1") (pintype "passive"))
    )
    (net (code "103") (name "Net-(IC4-LED)") (class "Default")
      (node (ref "F4") (pin "1") (pinfunction "1_1") (pintype "passive"))
      (node (ref "IC4") (pin "5") (pinfunction "LED_5") (pintype "power_in"))
    )
    (net (code "104") (name "Net-(IC4-RSET)") (class "Default")
      (node (ref "IC4") (pin "4") (pinfunction "RSET_4") (pintype "input"))
      (node (ref "R66") (pin "1") (pinfunction "1_1") (pintype "passive"))
    )
    (net (code "105") (name "Net-(IC5-LED)") (class "Default")
      (node (ref "F3") (pin "1") (pinfunction "1_1") (pintype "passive"))
      (node (ref "IC5") (pin "5") (pinfunction "LED_5") (pintype "power_in"))
    )
    (net (code "106") (name "Net-(IC5-RSET)") (class "Default")
      (node (ref "IC5") (pin "4") (pinfunction "RSET_4") (pintype "input"))
      (node (ref "R73") (pin "1") (pinfunction "1_1") (pintype "passive"))
    )
    (net (code "107") (name "Net-(IC6-LED)") (class "Default")
      (node (ref "F2") (pin "1") (pinfunction "1_1") (pintype "passive"))
      (node (ref "IC6") (pin "5") (pinfunction "LED_5") (pintype "power_in"))
    )
    (net (code "108") (name "Net-(IC6-RSET)") (class "Default")
      (node (ref "IC6") (pin "4") (pinfunction "RSET_4") (pintype "input"))
      (node (ref "R76") (pin "1") (pinfunction "1_1") (pintype "passive"))
    )
    (net (code "109") (name "Net-(LED1-PadA)") (class "Default")
      (node (ref "LED1") (pin "A") (pinfunction "A_A") (pintype "passive"))
      (node (ref "R65") (pin "2") (pinfunction "2_2") (pintype "passive"))
    )
    (net (code "110") (name "Net-(LED2-PadA)") (class "Default")
      (node (ref "LED2") (pin "A") (pinfunction "A_A") (pintype "passive"))
      (node (ref "R68") (pin "2") (pinfunction "2_2") (pintype "passive"))
    )
    (net (code "111") (name "Net-(LED3-PadA)") (class "Default")
      (node (ref "LED3") (pin "A") (pinfunction "A_A") (pintype "passive"))
      (node (ref "R69") (pin "2") (pinfunction "2_2") (pintype "passive"))
    )
    (net (code "112") (name "Net-(LED4-PadA)") (class "Default")
      (node (ref "LED4") (pin "A") (pinfunction "A_A") (pintype "passive"))
      (node (ref "R70") (pin "1") (pinfunction "1_1") (pintype "passive"))
    )
    (net (code "113") (name "Net-(LED5-PadA)") (class "Default")
      (node (ref "LED5") (pin "A") (pinfunction "A_A") (pintype "passive"))
      (node (ref "R72") (pin "2") (pinfunction "2_2") (pintype "passive"))
    )
    (net (code "114") (name "Net-(LED6-PadA)") (class "Default")
      (node (ref "LED6") (pin "A") (pinfunction "A_A") (pintype "passive"))
      (node (ref "R75") (pin "2") (pinfunction "2_2") (pintype "passive"))
    )
    (net (code "115") (name "Net-(Q1-PadB)") (class "Default")
      (node (ref "Q1") (pin "B") (pinfunction "B_B") (pintype "passive"))
      (node (ref "R50") (pin "2") (pinfunction "2_2") (pintype "passive"))
    )
    (net (code "116") (name "Net-(Q2-PadB)") (class "Default")
      (node (ref "Q2") (pin "B") (pinfunction "B_B") (pintype "passive"))
      (node (ref "R52") (pin "2") (pinfunction "2_2") (pintype "passive"))
    )
    (net (code "117") (name "Net-(Q3-PadB)") (class "Default")
      (node (ref "Q3") (pin "B") (pinfunction "B_B") (pintype "passive"))
      (node (ref "R54") (pin "2") (pinfunction "2_2") (pintype "passive"))
    )
    (net (code "118") (name "Net-(Q4-PadB)") (class "Default")
      (node (ref "Q4") (pin "B") (pinfunction "B_B") (pintype "passive"))
      (node (ref "R56") (pin "2") (pinfunction "2_2") (pintype "passive"))
    )
    (net (code "119") (name "Net-(Q5-PadB)") (class "Default")
      (node (ref "Q5") (pin "B") (pinfunction "B_B") (pintype "passive"))
      (node (ref "R58") (pin "2") (pinfunction "2_2") (pintype "passive"))
    )
    (net (code "120") (name "Net-(Q6-PadB)") (class "Default")
      (node (ref "Q6") (pin "B") (pinfunction "B_B") (pintype "passive"))
      (node (ref "R60") (pin "2") (pinfunction "2_2") (pintype "passive"))
    )
    (net (code "121") (name "Net-(Q7-PadB)") (class "Default")
      (node (ref "Q7") (pin "B") (pinfunction "B_B") (pintype "passive"))
      (node (ref "R62") (pin "2") (pinfunction "2_2") (pintype "passive"))
    )
    (net (code "122") (name "Net-(Q8-PadB)") (class "Default")
      (node (ref "Q8") (pin "B") (pinfunction "B_B") (pintype "passive"))
      (node (ref "R64") (pin "2") (pinfunction "2_2") (pintype "passive"))
    )
    (net (code "123") (name "Net-(T1-D)") (class "Default")
      (node (ref "T1") (pin "1") (pinfunction "D_1") (pintype "passive"))
      (node (ref "X1") (pin "1") (pinfunction "S_1") (pintype "passive"))
    )
    (net (code "124") (name "Net-(T1-G)") (class "Default")
      (node (ref "R1") (pin "2") (pinfunction "2_2") (pintype "passive"))
      (node (ref "T1") (pin "3") (pinfunction "G_3") (pintype "passive"))
    )
    (net (code "125") (name "Net-(T2-D)") (class "Default")
      (node (ref "T2") (pin "1") (pinfunction "D_1") (pintype "passive"))
      (node (ref "X1") (pin "2") (pinfunction "S_2") (pintype "passive"))
    )
    (net (code "126") (name "Net-(T2-G)") (class "Default")
      (node (ref "R3") (pin "2") (pinfunction "2_2") (pintype "passive"))
      (node (ref "T2") (pin "3") (pinfunction "G_3") (pintype "passive"))
    )
    (net (code "127") (name "Net-(T3-D)") (class "Default")
      (node (ref "T3") (pin "1") (pinfunction "D_1") (pintype "passive"))
      (node (ref "X1") (pin "3") (pinfunction "S_3") (pintype "passive"))
    )
    (net (code "128") (name "Net-(T3-G)") (class "Default")
      (node (ref "R5") (pin "2") (pinfunction "2_2") (pintype "passive"))
      (node (ref "T3") (pin "3") (pinfunction "G_3") (pintype "passive"))
    )
    (net (code "129") (name "Net-(T4-D)") (class "Default")
      (node (ref "T4") (pin "1") (pinfunction "D_1") (pintype "passive"))
      (node (ref "X1") (pin "4") (pinfunction "S_4") (pintype "passive"))
    )
    (net (code "130") (name "Net-(T4-G)") (class "Default")
      (node (ref "R7") (pin "2") (pinfunction "2_2") (pintype "passive"))
      (node (ref "T4") (pin "3") (pinfunction "G_3") (pintype "passive"))
    )
    (net (code "131") (name "Net-(T5-D)") (class "Default")
      (node (ref "T5") (pin "1") (pinfunction "D_1") (pintype "passive"))
      (node (ref "X1") (pin "5") (pinfunction "S_5") (pintype "passive"))
    )
    (net (code "132") (name "Net-(T5-G)") (class "Default")
      (node (ref "R9") (pin "2") (pinfunction "2_2") (pintype "passive"))
      (node (ref "T5") (pin "3") (pinfunction "G_3") (pintype "passive"))
    )
    (net (code "133") (name "Net-(T6-D)") (class "Default")
      (node (ref "T6") (pin "1") (pinfunction "D_1") (pintype "passive"))
      (node (ref "X1") (pin "6") (pinfunction "S_6") (pintype "passive"))
    )
    (net (code "134") (name "Net-(T6-G)") (class "Default")
      (node (ref "R11") (pin "2") (pinfunction "2_2") (pintype "passive"))
      (node (ref "T6") (pin "3") (pinfunction "G_3") (pintype "passive"))
    )
    (net (code "135") (name "Net-(T7-D)") (class "Default")
      (node (ref "T7") (pin "1") (pinfunction "D_1") (pintype "passive"))
      (node (ref "X1") (pin "7") (pinfunction "S_7") (pintype "passive"))
    )
    (net (code "136") (name "Net-(T7-G)") (class "Default")
      (node (ref "R13") (pin "2") (pinfunction "2_2") (pintype "passive"))
      (node (ref "T7") (pin "3") (pinfunction "G_3") (pintype "passive"))
    )
    (net (code "137") (name "Net-(T8-D)") (class "Default")
      (node (ref "T8") (pin "1") (pinfunction "D_1") (pintype "passive"))
      (node (ref "X1") (pin "8") (pinfunction "S_8") (pintype "passive"))
    )
    (net (code "138") (name "Net-(T8-G)") (class "Default")
      (node (ref "R15") (pin "2") (pinfunction "2_2") (pintype "passive"))
      (node (ref "T8") (pin "3") (pinfunction "G_3") (pintype "passive"))
    )
    (net (code "139") (name "Net-(T9-D)") (class "Default")
      (node (ref "T9") (pin "1") (pinfunction "D_1") (pintype "passive"))
      (node (ref "X2") (pin "1") (pinfunction "S_1") (pintype "passive"))
    )
    (net (code "140") (name "Net-(T9-G)") (class "Default")
      (node (ref "R17") (pin "2") (pinfunction "2_2") (pintype "passive"))
      (node (ref "T9") (pin "3") (pinfunction "G_3") (pintype "passive"))
    )
    (net (code "141") (name "Net-(T10-D)") (class "Default")
      (node (ref "T10") (pin "1") (pinfunction "D_1") (pintype "passive"))
      (node (ref "X2") (pin "2") (pinfunction "S_2") (pintype "passive"))
    )
    (net (code "142") (name "Net-(T10-G)") (class "Default")
      (node (ref "R19") (pin "2") (pinfunction "2_2") (pintype "passive"))
      (node (ref "T10") (pin "3") (pinfunction "G_3") (pintype "passive"))
    )
    (net (code "143") (name "Net-(T11-D)") (class "Default")
      (node (ref "T11") (pin "1") (pinfunction "D_1") (pintype "passive"))
      (node (ref "X2") (pin "3") (pinfunction "S_3") (pintype "passive"))
    )
    (net (code "144") (name "Net-(T11-G)") (class "Default")
      (node (ref "R21") (pin "2") (pinfunction "2_2") (pintype "passive"))
      (node (ref "T11") (pin "3") (pinfunction "G_3") (pintype "passive"))
    )
    (net (code "145") (name "Net-(T12-D)") (class "Default")
      (node (ref "T12") (pin "1") (pinfunction "D_1") (pintype "passive"))
      (node (ref "X2") (pin "4") (pinfunction "S_4") (pintype "passive"))
    )
    (net (code "146") (name "Net-(T12-G)") (class "Default")
      (node (ref "R23") (pin "2") (pinfunction "2_2") (pintype "passive"))
      (node (ref "T12") (pin "3") (pinfunction "G_3") (pintype "passive"))
    )
    (net (code "147") (name "Net-(T13-D)") (class "Default")
      (node (ref "T13") (pin "1") (pinfunction "D_1") (pintype "passive"))
      (node (ref "X2") (pin "5") (pinfunction "S_5") (pintype "passive"))
    )
    (net (code "148") (name "Net-(T13-G)") (class "Default")
      (node (ref "R25") (pin "2") (pinfunction "2_2") (pintype "passive"))
      (node (ref "T13") (pin "3") (pinfunction "G_3") (pintype "passive"))
    )
    (net (code "149") (name "Net-(T14-D)") (class "Default")
      (node (ref "T14") (pin "1") (pinfunction "D_1") (pintype "passive"))
      (node (ref "X2") (pin "6") (pinfunction "S_6") (pintype "passive"))
    )
    (net (code "150") (name "Net-(T14-G)") (class "Default")
      (node (ref "R27") (pin "2") (pinfunction "2_2") (pintype "passive"))
      (node (ref "T14") (pin "3") (pinfunction "G_3") (pintype "passive"))
    )
    (net (code "151") (name "Net-(T15-D)") (class "Default")
      (node (ref "T15") (pin "1") (pinfunction "D_1") (pintype "passive"))
      (node (ref "X2") (pin "7") (pinfunction "S_7") (pintype "passive"))
    )
    (net (code "152") (name "Net-(T15-G)") (class "Default")
      (node (ref "R29") (pin "2") (pinfunction "2_2") (pintype "passive"))
      (node (ref "T15") (pin "3") (pinfunction "G_3") (pintype "passive"))
    )
    (net (code "153") (name "Net-(T16-D)") (class "Default")
      (node (ref "T16") (pin "1") (pinfunction "D_1") (pintype "passive"))
      (node (ref "X2") (pin "8") (pinfunction "S_8") (pintype "passive"))
    )
    (net (code "154") (name "Net-(T16-G)") (class "Default")
      (node (ref "R31") (pin "2") (pinfunction "2_2") (pintype "passive"))
      (node (ref "T16") (pin "3") (pinfunction "G_3") (pintype "passive"))
    )
    (net (code "155") (name "Net-(T17-D)") (class "Default")
      (node (ref "T17") (pin "1") (pinfunction "D_1") (pintype "passive"))
      (node (ref "X3") (pin "1") (pinfunction "S_1") (pintype "passive"))
    )
    (net (code "156") (name "Net-(T17-G)") (class "Default")
      (node (ref "R33") (pin "2") (pinfunction "2_2") (pintype "passive"))
      (node (ref "T17") (pin "3") (pinfunction "G_3") (pintype "passive"))
    )
    (net (code "157") (name "Net-(T18-D)") (class "Default")
      (node (ref "T18") (pin "1") (pinfunction "D_1") (pintype "passive"))
      (node (ref "X3") (pin "2") (pinfunction "S_2") (pintype "passive"))
    )
    (net (code "158") (name "Net-(T18-G)") (class "Default")
      (node (ref "R35") (pin "2") (pinfunction "2_2") (pintype "passive"))
      (node (ref "T18") (pin "3") (pinfunction "G_3") (pintype "passive"))
    )
    (net (code "159") (name "Net-(T19-D)") (class "Default")
      (node (ref "T19") (pin "1") (pinfunction "D_1") (pintype "passive"))
      (node (ref "X3") (pin "3") (pinfunction "S_3") (pintype "passive"))
    )
    (net (code "160") (name "Net-(T19-G)") (class "Default")
      (node (ref "R37") (pin "2") (pinfunction "2_2") (pintype "passive"))
      (node (ref "T19") (pin "3") (pinfunction "G_3") (pintype "passive"))
    )
    (net (code "161") (name "Net-(T20-D)") (class "Default")
      (node (ref "T20") (pin "1") (pinfunction "D_1") (pintype "passive"))
      (node (ref "X3") (pin "4") (pinfunction "S_4") (pintype "passive"))
    )
    (net (code "162") (name "Net-(T20-G)") (class "Default")
      (node (ref "R39") (pin "2") (pinfunction "2_2") (pintype "passive"))
      (node (ref "T20") (pin "3") (pinfunction "G_3") (pintype "passive"))
    )
    (net (code "163") (name "Net-(T21-D)") (class "Default")
      (node (ref "T21") (pin "1") (pinfunction "D_1") (pintype "passive"))
      (node (ref "X3") (pin "5") (pinfunction "S_5") (pintype "passive"))
    )
    (net (code "164") (name "Net-(T21-G)") (class "Default")
      (node (ref "R41") (pin "2") (pinfunction "2_2") (pintype "passive"))
      (node (ref "T21") (pin "3") (pinfunction "G_3") (pintype "passive"))
    )
    (net (code "165") (name "Net-(T22-D)") (class "Default")
      (node (ref "T22") (pin "1") (pinfunction "D_1") (pintype "passive"))
      (node (ref "X3") (pin "6") (pinfunction "S_6") (pintype "passive"))
    )
    (net (code "166") (name "Net-(T22-G)") (class "Default")
      (node (ref "R43") (pin "2") (pinfunction "2_2") (pintype "passive"))
      (node (ref "T22") (pin "3") (pinfunction "G_3") (pintype "passive"))
    )
    (net (code "167") (name "Net-(T23-D)") (class "Default")
      (node (ref "T23") (pin "1") (pinfunction "D_1") (pintype "passive"))
      (node (ref "X3") (pin "7") (pinfunction "S_7") (pintype "passive"))
    )
    (net (code "168") (name "Net-(T23-G)") (class "Default")
      (node (ref "R45") (pin "2") (pinfunction "2_2") (pintype "passive"))
      (node (ref "T23") (pin "3") (pinfunction "G_3") (pintype "passive"))
    )
    (net (code "169") (name "Net-(T24-D)") (class "Default")
      (node (ref "T24") (pin "1") (pinfunction "D_1") (pintype "passive"))
      (node (ref "X3") (pin "8") (pinfunction "S_8") (pintype "passive"))
    )
    (net (code "170") (name "Net-(T24-G)") (class "Default")
      (node (ref "R47") (pin "2") (pinfunction "2_2") (pintype "passive"))
      (node (ref "T24") (pin "3") (pinfunction "G_3") (pintype "passive"))
    )
    (net (code "171") (name "Net-(T25-D)") (class "Default")
      (node (ref "T25") (pin "1") (pinfunction "D_1") (pintype "passive"))
      (node (ref "X4") (pin "1") (pinfunction "S_1") (pintype "passive"))
    )
    (net (code "172") (name "Net-(T25-G)") (class "Default")
      (node (ref "Q1") (pin "C") (pinfunction "C_C") (pintype "passive"))
      (node (ref "R49") (pin "1") (pinfunction "1_1") (pintype "passive"))
      (node (ref "T25") (pin "3") (pinfunction "G_3") (pintype "passive"))
    )
    (net (code "173") (name "Net-(T26-D)") (class "Default")
      (node (ref "T26") (pin "1") (pinfunction "D_1") (pintype "passive"))
      (node (ref "X4") (pin "2") (pinfunction "S_2") (pintype "passive"))
    )
    (net (code "174") (name "Net-(T26-G)") (class "Default")
      (node (ref "Q2") (pin "C") (pinfunction "C_C") (pintype "passive"))
      (node (ref "R51") (pin "1") (pinfunction "1_1") (pintype "passive"))
      (node (ref "T26") (pin "3") (pinfunction "G_3") (pintype "passive"))
    )
    (net (code "175") (name "Net-(T27-D)") (class "Default")
      (node (ref "T27") (pin "1") (pinfunction "D_1") (pintype "passive"))
      (node (ref "X4") (pin "3") (pinfunction "S_3") (pintype "passive"))
    )
    (net (code "176") (name "Net-(T27-G)") (class "Default")
      (node (ref "Q3") (pin "C") (pinfunction "C_C") (pintype "passive"))
      (node (ref "R53") (pin "1") (pinfunction "1_1") (pintype "passive"))
      (node (ref "T27") (pin "3") (pinfunction "G_3") (pintype "passive"))
    )
    (net (code "177") (name "Net-(T28-D)") (class "Default")
      (node (ref "T28") (pin "1") (pinfunction "D_1") (pintype "passive"))
      (node (ref "X4") (pin "4") (pinfunction "S_4") (pintype "passive"))
    )
    (net (code "178") (name "Net-(T28-G)") (class "Default")
      (node (ref "Q4") (pin "C") (pinfunction "C_C") (pintype "passive"))
      (node (ref "R55") (pin "1") (pinfunction "1_1") (pintype "passive"))
      (node (ref "T28") (pin "3") (pinfunction "G_3") (pintype "passive"))
    )
    (net (code "179") (name "Net-(T29-D)") (class "Default")
      (node (ref "T29") (pin "1") (pinfunction "D_1") (pintype "passive"))
      (node (ref "X4") (pin "5") (pinfunction "S_5") (pintype "passive"))
    )
    (net (code "180") (name "Net-(T29-G)") (class "Default")
      (node (ref "Q5") (pin "C") (pinfunction "C_C") (pintype "passive"))
      (node (ref "R57") (pin "1") (pinfunction "1_1") (pintype "passive"))
      (node (ref "T29") (pin "3") (pinfunction "G_3") (pintype "passive"))
    )
    (net (code "181") (name "Net-(T30-D)") (class "Default")
      (node (ref "T30") (pin "1") (pinfunction "D_1") (pintype "passive"))
      (node (ref "X4") (pin "6") (pinfunction "S_6") (pintype "passive"))
    )
    (net (code "182") (name "Net-(T30-G)") (class "Default")
      (node (ref "Q6") (pin "C") (pinfunction "C_C") (pintype "passive"))
      (node (ref "R59") (pin "1") (pinfunction "1_1") (pintype "passive"))
      (node (ref "T30") (pin "3") (pinfunction "G_3") (pintype "passive"))
    )
    (net (code "183") (name "Net-(T31-D)") (class "Default")
      (node (ref "T31") (pin "1") (pinfunction "D_1") (pintype "passive"))
      (node (ref "X4") (pin "7") (pinfunction "S_7") (pintype "passive"))
    )
    (net (code "184") (name "Net-(T31-G)") (class "Default")
      (node (ref "Q7") (pin "C") (pinfunction "C_C") (pintype "passive"))
      (node (ref "R61") (pin "1") (pinfunction "1_1") (pintype "passive"))
      (node (ref "T31") (pin "3") (pinfunction "G_3") (pintype "passive"))
    )
    (net (code "185") (name "Net-(T32-D)") (class "Default")
      (node (ref "T32") (pin "1") (pinfunction "D_1") (pintype "passive"))
      (node (ref "X4") (pin "8") (pinfunction "S_8") (pintype "passive"))
    )
    (net (code "186") (name "Net-(T32-G)") (class "Default")
      (node (ref "Q8") (pin "C") (pinfunction "C_C") (pintype "passive"))
      (node (ref "R63") (pin "1") (pinfunction "1_1") (pintype "passive"))
      (node (ref "T32") (pin "3") (pinfunction "G_3") (pintype "passive"))
    )
    (net (code "187") (name "VCC") (class "Default")
      (node (ref "5V") (pin "2") (pinfunction "2_2") (pintype "passive"))
      (node (ref "J1") (pin "2") (pinfunction "2_2") (pintype "power_in"))
      (node (ref "JP1") (pin "1") (pinfunction "1_1") (pintype "passive"))
      (node (ref "JP2") (pin "1") (pinfunction "1_1") (pintype "passive"))
      (node (ref "JP2") (pin "2") (pinfunction "2_2") (pintype "passive"))
    )
  )
)
